# Analog.net
KiCad netlist of a schematic drawn in Altium Designer
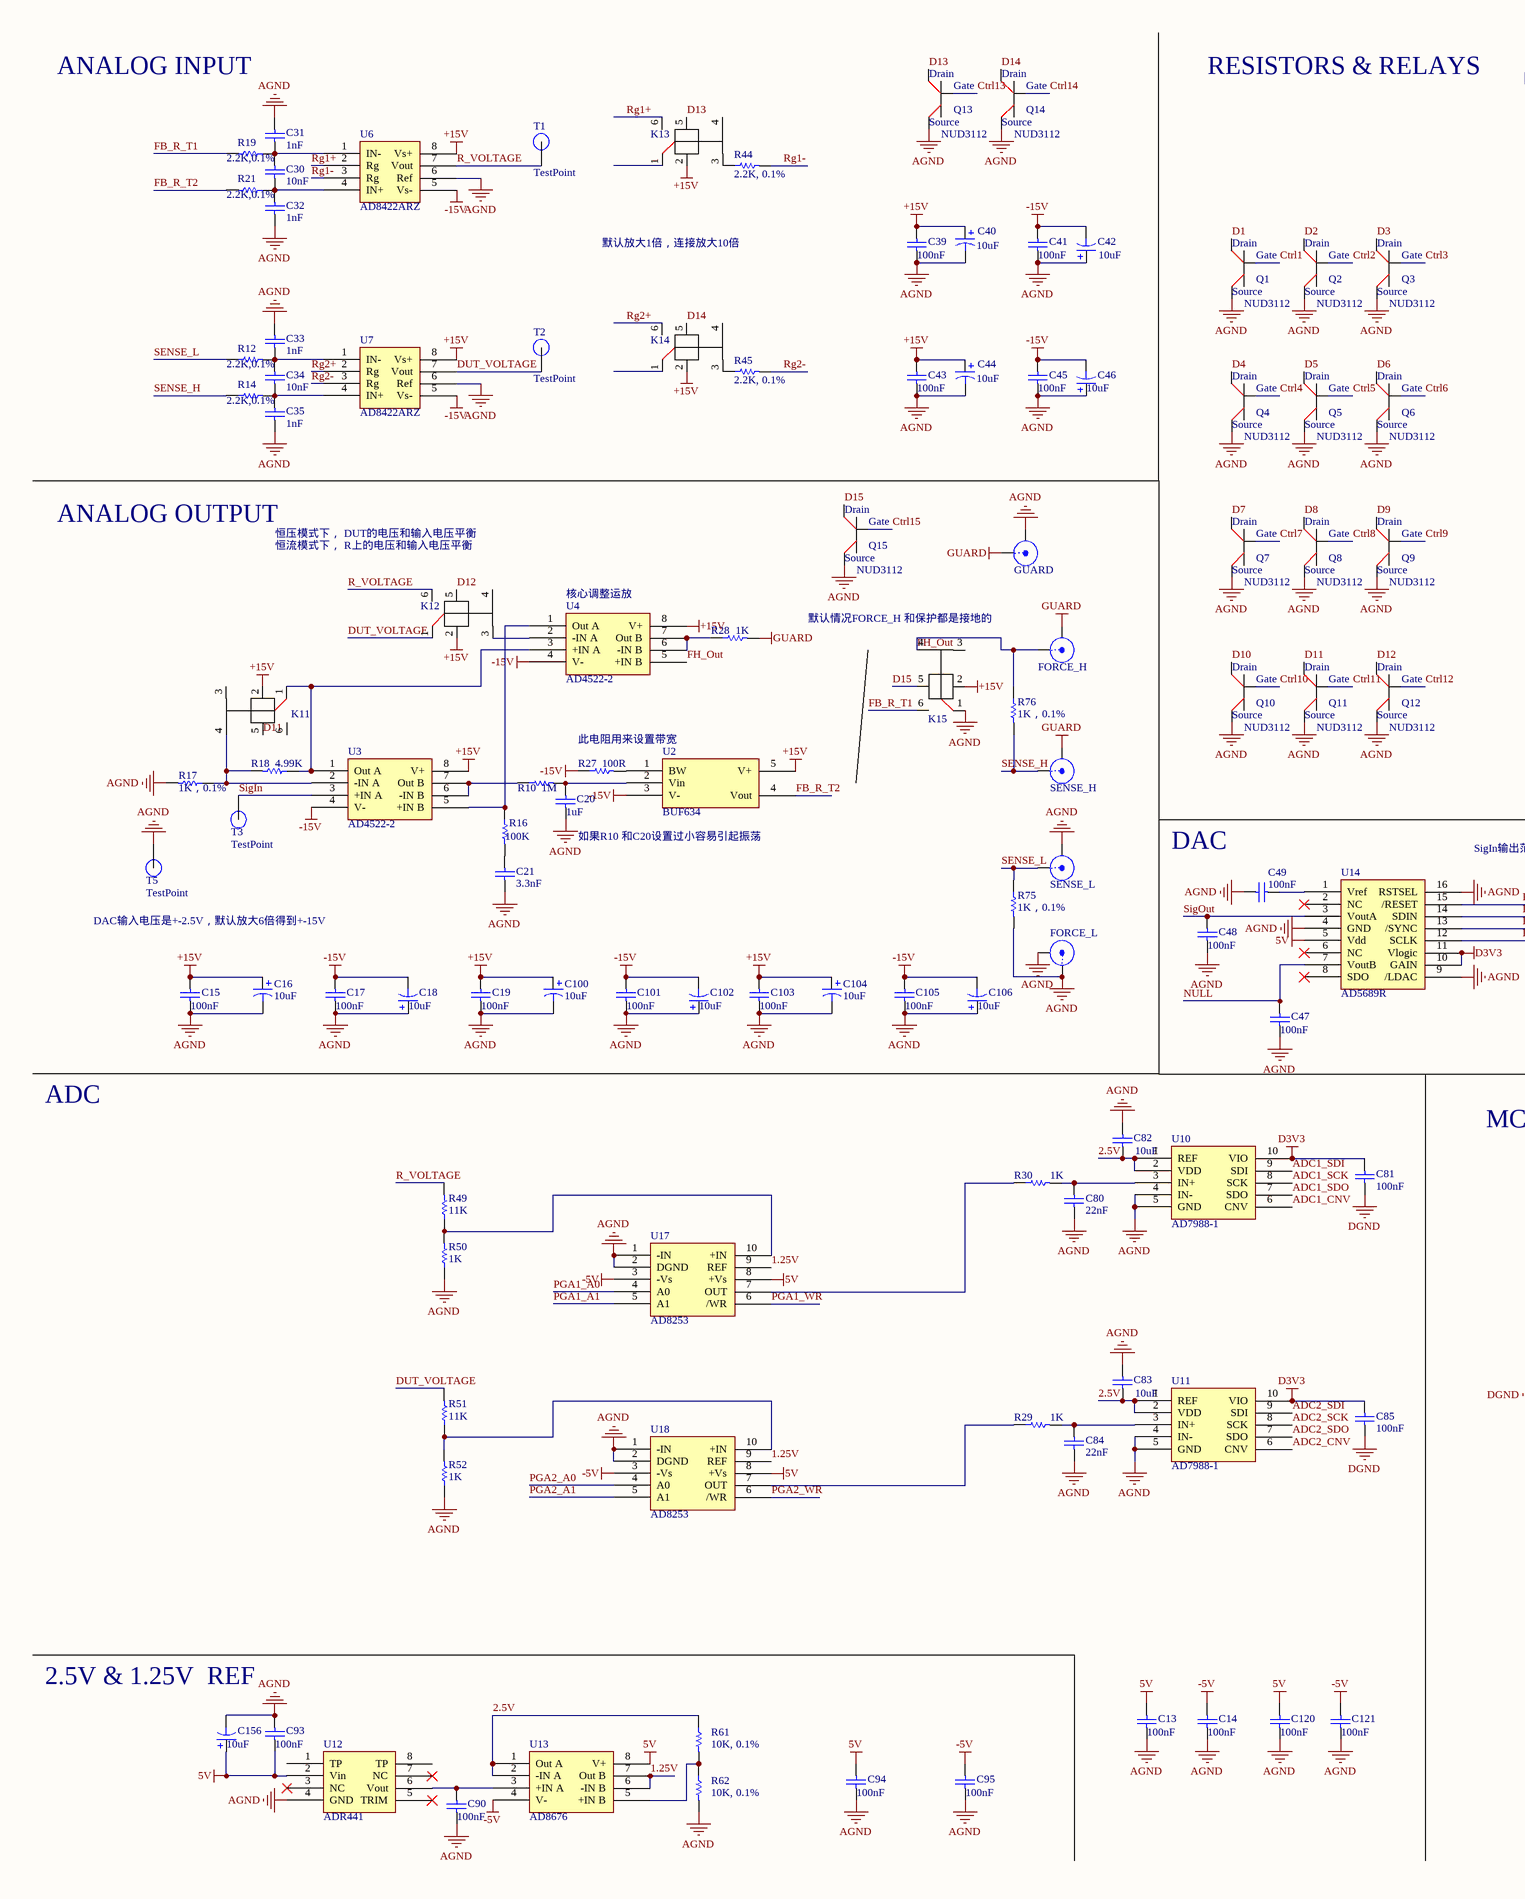
[diagram p0: Analog.SchDoc, left]
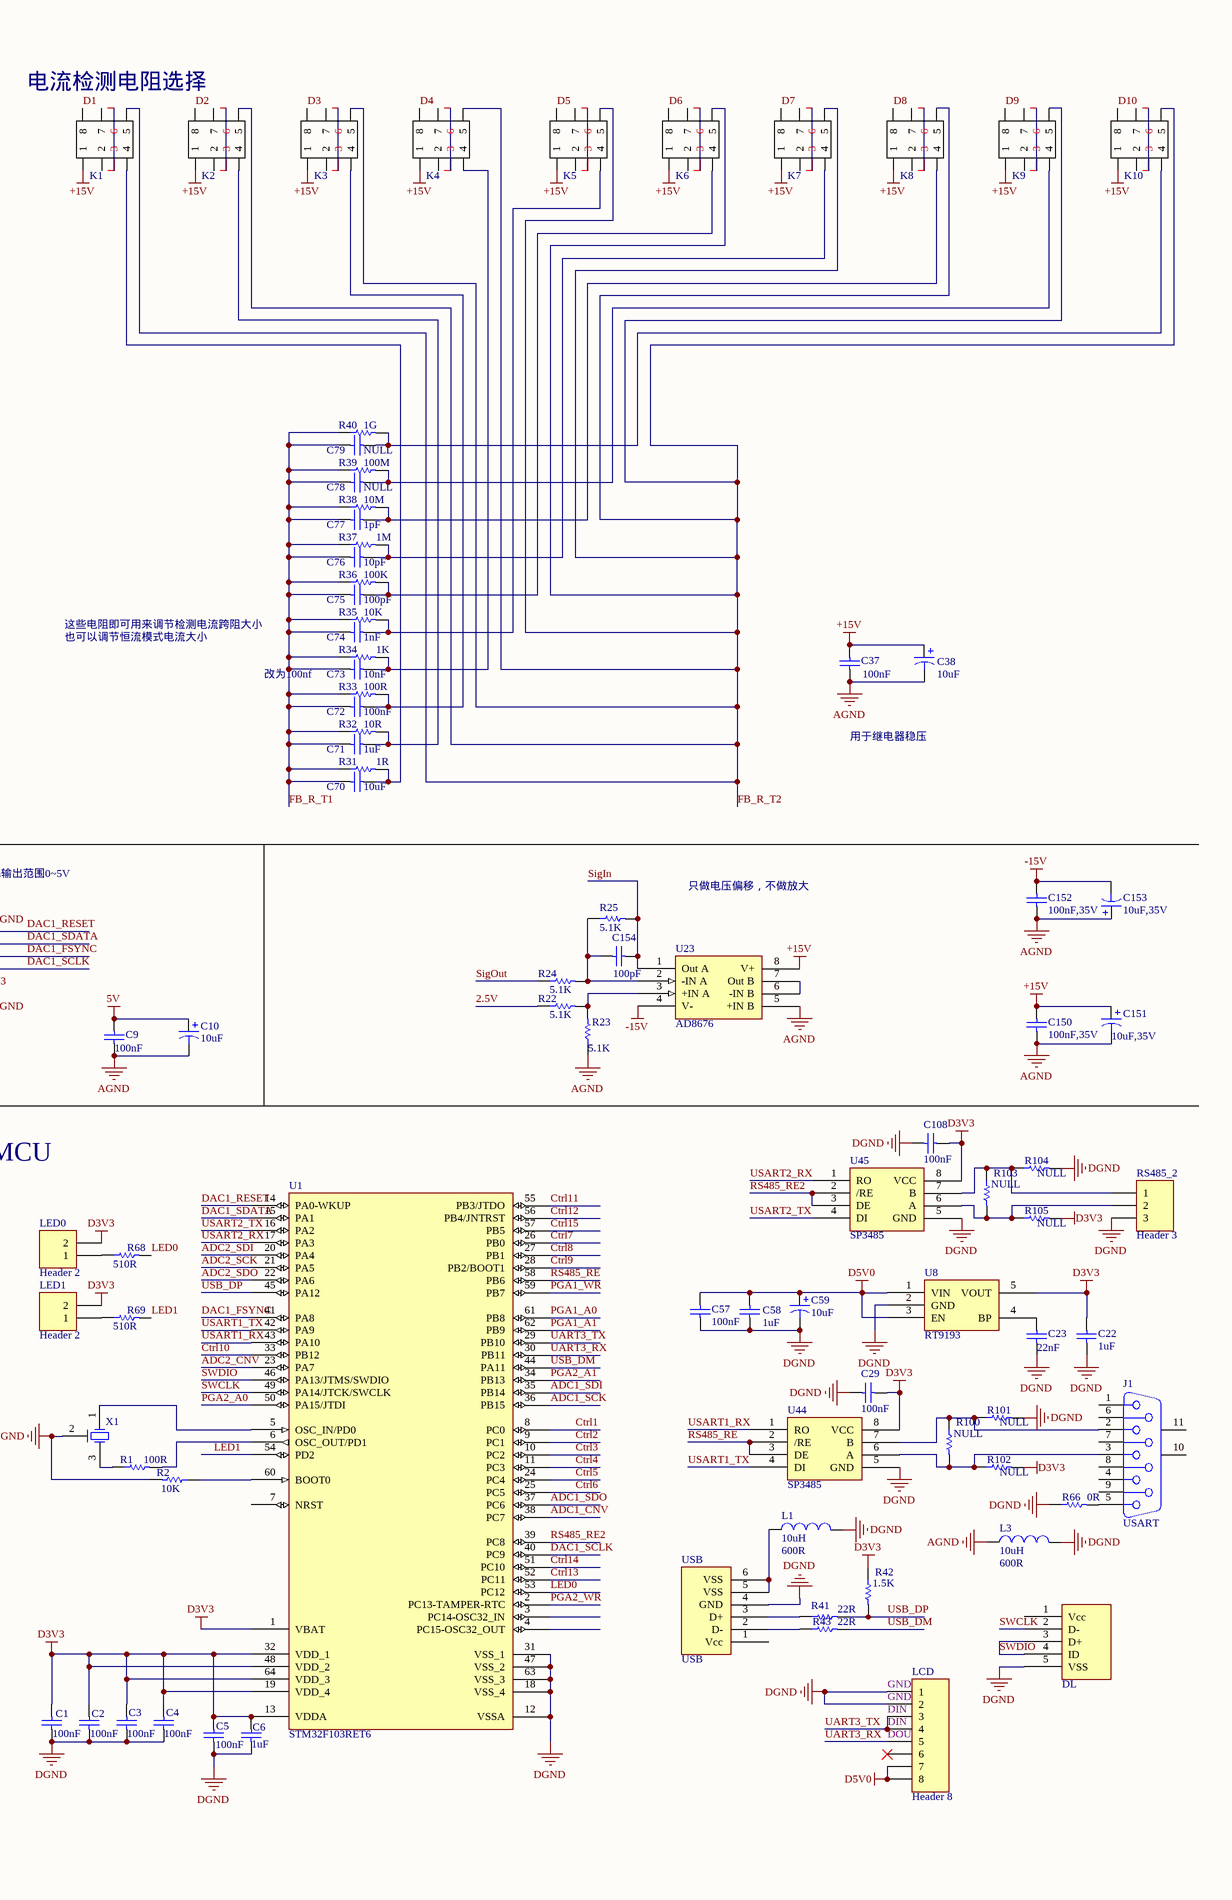
[diagram p1: Analog.SchDoc, right]

(export (version "E")
  (design (tool "Eeschema 10.0.6"))
  (components
    (comp (ref "C1")
      (value "100nF")
      (footprint "BinFeng:0603")
      (description "Capacitor")
      (fields (field (name "PUBLISHER") "Altium Limited"))
      (libsource (lib "Miscellaneous Devices") (part "Cap"))
    )
    (comp (ref "C2")
      (value "100nF")
      (footprint "BinFeng:0603")
      (description "Capacitor")
      (fields (field (name "PUBLISHER") "Altium Limited"))
      (libsource (lib "Miscellaneous Devices") (part "Cap"))
    )
    (comp (ref "C3")
      (value "100nF")
      (footprint "BinFeng:0603")
      (description "Capacitor")
      (fields (field (name "PUBLISHER") "Altium Limited"))
      (libsource (lib "Miscellaneous Devices") (part "Cap"))
    )
    (comp (ref "C4")
      (value "100nF")
      (footprint "BinFeng:0603")
      (description "Capacitor")
      (fields (field (name "PUBLISHER") "Altium Limited"))
      (libsource (lib "Miscellaneous Devices") (part "Cap"))
    )
    (comp (ref "C5")
      (value "100nF")
      (footprint "BinFeng:0603")
      (description "Capacitor")
      (fields (field (name "PUBLISHER") "Altium Limited"))
      (libsource (lib "Miscellaneous Devices") (part "Cap"))
    )
    (comp (ref "C6")
      (value "1uF")
      (footprint "BinFeng:0603")
      (description "Capacitor")
      (fields (field (name "PUBLISHER") "Altium Limited"))
      (libsource (lib "Miscellaneous Devices") (part "Cap"))
    )
    (comp (ref "C9")
      (value "100nF")
      (footprint "0805")
      (description "Capacitor")
      (fields (field (name "PUBLISHER") "Altium Limited"))
      (libsource (lib "Miscellaneous Devices") (part "Cap"))
    )
    (comp (ref "C10")
      (value "10uF")
      (footprint "6032_pol")
      (description "Polarized Capacitor (Radial)")
      (fields (field (name "PUBLISHER") "Altium Limited"))
      (libsource (lib "Miscellaneous Devices") (part "Cap Pol1"))
    )
    (comp (ref "C13")
      (value "100nF")
      (footprint "BinFeng:0603")
      (description "Capacitor")
      (fields (field (name "PUBLISHER") "Altium Limited"))
      (libsource (lib "Miscellaneous Devices") (part "Cap"))
    )
    (comp (ref "C14")
      (value "100nF")
      (footprint "BinFeng:0603")
      (description "Capacitor")
      (fields (field (name "PUBLISHER") "Altium Limited"))
      (libsource (lib "Miscellaneous Devices") (part "Cap"))
    )
    (comp (ref "C15")
      (value "100nF")
      (footprint "0805")
      (description "Capacitor")
      (fields (field (name "PUBLISHER") "Altium Limited"))
      (libsource (lib "Miscellaneous Devices") (part "Cap"))
    )
    (comp (ref "C16")
      (value "10uF")
      (footprint "6032_pol")
      (description "Polarized Capacitor (Radial)")
      (fields (field (name "PUBLISHER") "Altium Limited"))
      (libsource (lib "Miscellaneous Devices") (part "Cap Pol1"))
    )
    (comp (ref "C17")
      (value "100nF")
      (footprint "0805")
      (description "Capacitor")
      (fields (field (name "PUBLISHER") "Altium Limited"))
      (libsource (lib "Miscellaneous Devices") (part "Cap"))
    )
    (comp (ref "C18")
      (value "10uF")
      (footprint "6032_pol")
      (description "Polarized Capacitor (Radial)")
      (fields (field (name "PUBLISHER") "Altium Limited"))
      (libsource (lib "Miscellaneous Devices") (part "Cap Pol1"))
    )
    (comp (ref "C19")
      (value "100nF")
      (footprint "0805")
      (description "Capacitor")
      (fields (field (name "PUBLISHER") "Altium Limited"))
      (libsource (lib "Miscellaneous Devices") (part "Cap"))
    )
    (comp (ref "C20")
      (value "1uF")
      (footprint "BinFeng:0603")
      (description "Capacitor")
      (fields (field (name "PUBLISHER") "Altium Limited"))
      (libsource (lib "Miscellaneous Devices") (part "Cap"))
    )
    (comp (ref "C21")
      (value "3.3nF")
      (footprint "BinFeng:0603")
      (description "Capacitor")
      (fields (field (name "PUBLISHER") "Altium Limited"))
      (libsource (lib "Miscellaneous Devices") (part "Cap"))
    )
    (comp (ref "C22")
      (value "1uF")
      (footprint "BinFeng:0603")
      (description "Capacitor")
      (fields (field (name "PUBLISHER") "Altium Limited"))
      (libsource (lib "Miscellaneous Devices") (part "Cap"))
    )
    (comp (ref "C23")
      (value "22nF")
      (footprint "BinFeng:0603")
      (description "Capacitor")
      (fields (field (name "PUBLISHER") "Altium Limited"))
      (libsource (lib "Miscellaneous Devices") (part "Cap"))
    )
    (comp (ref "C29")
      (value "100nF")
      (footprint "BinFeng:0603")
      (description "Capacitor")
      (fields (field (name "PUBLISHER") "Altium Limited"))
      (libsource (lib "Miscellaneous Devices") (part "Cap"))
    )
    (comp (ref "C30")
      (value "10nF")
      (footprint "BinFeng:0603")
      (description "Capacitor")
      (fields (field (name "PUBLISHER") "Altium Limited"))
      (libsource (lib "Miscellaneous Devices") (part "Cap"))
    )
    (comp (ref "C31")
      (value "1nF")
      (footprint "BinFeng:0603")
      (description "Capacitor")
      (fields (field (name "PUBLISHER") "Altium Limited"))
      (libsource (lib "Miscellaneous Devices") (part "Cap"))
    )
    (comp (ref "C32")
      (value "1nF")
      (footprint "BinFeng:0603")
      (description "Capacitor")
      (fields (field (name "PUBLISHER") "Altium Limited"))
      (libsource (lib "Miscellaneous Devices") (part "Cap"))
    )
    (comp (ref "C33")
      (value "1nF")
      (footprint "BinFeng:0603")
      (description "Capacitor")
      (fields (field (name "PUBLISHER") "Altium Limited"))
      (libsource (lib "Miscellaneous Devices") (part "Cap"))
    )
    (comp (ref "C34")
      (value "10nF")
      (footprint "BinFeng:0603")
      (description "Capacitor")
      (fields (field (name "PUBLISHER") "Altium Limited"))
      (libsource (lib "Miscellaneous Devices") (part "Cap"))
    )
    (comp (ref "C35")
      (value "1nF")
      (footprint "BinFeng:0603")
      (description "Capacitor")
      (fields (field (name "PUBLISHER") "Altium Limited"))
      (libsource (lib "Miscellaneous Devices") (part "Cap"))
    )
    (comp (ref "C37")
      (value "100nF")
      (footprint "0805")
      (description "Capacitor")
      (fields (field (name "PUBLISHER") "Altium Limited"))
      (libsource (lib "Miscellaneous Devices") (part "Cap"))
    )
    (comp (ref "C38")
      (value "10uF")
      (footprint "6032_pol")
      (description "Polarized Capacitor (Radial)")
      (fields (field (name "PUBLISHER") "Altium Limited"))
      (libsource (lib "Miscellaneous Devices") (part "Cap Pol1"))
    )
    (comp (ref "C39")
      (value "100nF")
      (footprint "0805")
      (description "Capacitor")
      (fields (field (name "PUBLISHER") "Altium Limited"))
      (libsource (lib "Miscellaneous Devices") (part "Cap"))
    )
    (comp (ref "C40")
      (value "10uF")
      (footprint "6032_pol")
      (description "Polarized Capacitor (Radial)")
      (fields (field (name "PUBLISHER") "Altium Limited"))
      (libsource (lib "Miscellaneous Devices") (part "Cap Pol1"))
    )
    (comp (ref "C41")
      (value "100nF")
      (footprint "0805")
      (description "Capacitor")
      (fields (field (name "PUBLISHER") "Altium Limited"))
      (libsource (lib "Miscellaneous Devices") (part "Cap"))
    )
    (comp (ref "C42")
      (value "10uF")
      (footprint "6032_pol")
      (description "Polarized Capacitor (Radial)")
      (fields (field (name "PUBLISHER") "Altium Limited"))
      (libsource (lib "Miscellaneous Devices") (part "Cap Pol1"))
    )
    (comp (ref "C43")
      (value "100nF")
      (footprint "0805")
      (description "Capacitor")
      (fields (field (name "PUBLISHER") "Altium Limited"))
      (libsource (lib "Miscellaneous Devices") (part "Cap"))
    )
    (comp (ref "C44")
      (value "10uF")
      (footprint "6032_pol")
      (description "Polarized Capacitor (Radial)")
      (fields (field (name "PUBLISHER") "Altium Limited"))
      (libsource (lib "Miscellaneous Devices") (part "Cap Pol1"))
    )
    (comp (ref "C45")
      (value "100nF")
      (footprint "0805")
      (description "Capacitor")
      (fields (field (name "PUBLISHER") "Altium Limited"))
      (libsource (lib "Miscellaneous Devices") (part "Cap"))
    )
    (comp (ref "C46")
      (value "10uF")
      (footprint "6032_pol")
      (description "Polarized Capacitor (Radial)")
      (fields (field (name "PUBLISHER") "Altium Limited"))
      (libsource (lib "Miscellaneous Devices") (part "Cap Pol1"))
    )
    (comp (ref "C47")
      (value "100nF")
      (footprint "BinFeng:0603")
      (description "Capacitor")
      (fields (field (name "PUBLISHER") "Altium Limited"))
      (libsource (lib "Miscellaneous Devices") (part "Cap"))
    )
    (comp (ref "C48")
      (value "100nF")
      (footprint "BinFeng:0603")
      (description "Capacitor")
      (fields (field (name "PUBLISHER") "Altium Limited"))
      (libsource (lib "Miscellaneous Devices") (part "Cap"))
    )
    (comp (ref "C49")
      (value "100nF")
      (footprint "BinFeng:0603")
      (description "Capacitor")
      (fields (field (name "PUBLISHER") "Altium Limited"))
      (libsource (lib "Miscellaneous Devices") (part "Cap"))
    )
    (comp (ref "C57")
      (value "100nF")
      (footprint "0805")
      (description "Capacitor,100V")
      (fields (field (name "PUBLISHER") "Altium Limited"))
      (libsource (lib "Miscellaneous Devices") (part "Cap"))
    )
    (comp (ref "C58")
      (value "1uF")
      (footprint "0805")
      (description "Capacitor")
      (fields (field (name "PUBLISHER") "Altium Limited"))
      (libsource (lib "Miscellaneous Devices") (part "Cap"))
    )
    (comp (ref "C59")
      (value "10uF")
      (footprint "6032_pol")
      (description "Polarized Capacitor (Radial)")
      (fields (field (name "PUBLISHER") "Altium Limited"))
      (libsource (lib "Miscellaneous Devices") (part "Cap Pol1"))
    )
    (comp (ref "C70")
      (value "10uF")
      (footprint "0805")
      (description "Capacitor")
      (fields (field (name "PUBLISHER") "Altium Limited"))
      (libsource (lib "Miscellaneous Devices") (part "Cap"))
    )
    (comp (ref "C71")
      (value "1uF")
      (footprint "0805")
      (description "Capacitor")
      (fields (field (name "PUBLISHER") "Altium Limited"))
      (libsource (lib "Miscellaneous Devices") (part "Cap"))
    )
    (comp (ref "C72")
      (value "100nF")
      (footprint "0805")
      (description "Capacitor")
      (fields (field (name "PUBLISHER") "Altium Limited"))
      (libsource (lib "Miscellaneous Devices") (part "Cap"))
    )
    (comp (ref "C73")
      (value "10nF")
      (footprint "0805")
      (description "Capacitor")
      (fields (field (name "PUBLISHER") "Altium Limited"))
      (libsource (lib "Miscellaneous Devices") (part "Cap"))
    )
    (comp (ref "C74")
      (value "1nF")
      (footprint "0805")
      (description "Capacitor")
      (fields (field (name "PUBLISHER") "Altium Limited"))
      (libsource (lib "Miscellaneous Devices") (part "Cap"))
    )
    (comp (ref "C75")
      (value "100pF")
      (footprint "0805")
      (description "Capacitor")
      (fields (field (name "PUBLISHER") "Altium Limited"))
      (libsource (lib "Miscellaneous Devices") (part "Cap"))
    )
    (comp (ref "C76")
      (value "10pF")
      (footprint "0805")
      (description "Capacitor")
      (fields (field (name "PUBLISHER") "Altium Limited"))
      (libsource (lib "Miscellaneous Devices") (part "Cap"))
    )
    (comp (ref "C77")
      (value "1pF")
      (footprint "0805")
      (description "Capacitor")
      (fields (field (name "PUBLISHER") "Altium Limited"))
      (libsource (lib "Miscellaneous Devices") (part "Cap"))
    )
    (comp (ref "C78")
      (value "NULL")
      (footprint "0805")
      (description "Capacitor")
      (fields (field (name "PUBLISHER") "Altium Limited"))
      (libsource (lib "Miscellaneous Devices") (part "Cap"))
    )
    (comp (ref "C79")
      (value "NULL")
      (footprint "0805")
      (description "Capacitor")
      (fields (field (name "PUBLISHER") "Altium Limited"))
      (libsource (lib "Miscellaneous Devices") (part "Cap"))
    )
    (comp (ref "C80")
      (value "22nF")
      (footprint "BinFeng:0603")
      (description "Capacitor")
      (fields (field (name "PUBLISHER") "Altium Limited"))
      (libsource (lib "Miscellaneous Devices") (part "Cap"))
    )
    (comp (ref "C81")
      (value "100nF")
      (footprint "BinFeng:0603")
      (description "Capacitor,100V")
      (fields (field (name "PUBLISHER") "Altium Limited"))
      (libsource (lib "Miscellaneous Devices") (part "Cap"))
    )
    (comp (ref "C82")
      (value "10uF")
      (footprint "0805")
      (description "Capacitor")
      (fields (field (name "PUBLISHER") "Altium Limited"))
      (libsource (lib "Miscellaneous Devices") (part "Cap"))
    )
    (comp (ref "C83")
      (value "10uF")
      (footprint "0805")
      (description "Capacitor")
      (fields (field (name "PUBLISHER") "Altium Limited"))
      (libsource (lib "Miscellaneous Devices") (part "Cap"))
    )
    (comp (ref "C84")
      (value "22nF")
      (footprint "BinFeng:0603")
      (description "Capacitor")
      (fields (field (name "PUBLISHER") "Altium Limited"))
      (libsource (lib "Miscellaneous Devices") (part "Cap"))
    )
    (comp (ref "C85")
      (value "100nF")
      (footprint "BinFeng:0603")
      (description "Capacitor,100V")
      (fields (field (name "PUBLISHER") "Altium Limited"))
      (libsource (lib "Miscellaneous Devices") (part "Cap"))
    )
    (comp (ref "C90")
      (value "100nF")
      (footprint "BinFeng:0603")
      (description "Capacitor")
      (fields (field (name "PUBLISHER") "Altium Limited"))
      (libsource (lib "Miscellaneous Devices") (part "Cap"))
    )
    (comp (ref "C93")
      (value "100nF")
      (footprint "BinFeng:0603")
      (description "Capacitor")
      (fields (field (name "PUBLISHER") "Altium Limited"))
      (libsource (lib "Miscellaneous Devices") (part "Cap"))
    )
    (comp (ref "C94")
      (value "100nF")
      (footprint "BinFeng:0603")
      (description "Capacitor")
      (fields (field (name "PUBLISHER") "Altium Limited"))
      (libsource (lib "Miscellaneous Devices") (part "Cap"))
    )
    (comp (ref "C95")
      (value "100nF")
      (footprint "BinFeng:0603")
      (description "Capacitor")
      (fields (field (name "PUBLISHER") "Altium Limited"))
      (libsource (lib "Miscellaneous Devices") (part "Cap"))
    )
    (comp (ref "C100")
      (value "10uF")
      (footprint "6032_pol")
      (description "Polarized Capacitor (Radial)")
      (fields (field (name "PUBLISHER") "Altium Limited"))
      (libsource (lib "Miscellaneous Devices") (part "Cap Pol1"))
    )
    (comp (ref "C101")
      (value "100nF")
      (footprint "0805")
      (description "Capacitor")
      (fields (field (name "PUBLISHER") "Altium Limited"))
      (libsource (lib "Miscellaneous Devices") (part "Cap"))
    )
    (comp (ref "C102")
      (value "10uF")
      (footprint "6032_pol")
      (description "Polarized Capacitor (Radial)")
      (fields (field (name "PUBLISHER") "Altium Limited"))
      (libsource (lib "Miscellaneous Devices") (part "Cap Pol1"))
    )
    (comp (ref "C103")
      (value "100nF")
      (footprint "0805")
      (description "Capacitor")
      (fields (field (name "PUBLISHER") "Altium Limited"))
      (libsource (lib "Miscellaneous Devices") (part "Cap"))
    )
    (comp (ref "C104")
      (value "10uF")
      (footprint "6032_pol")
      (description "Polarized Capacitor (Radial)")
      (fields (field (name "PUBLISHER") "Altium Limited"))
      (libsource (lib "Miscellaneous Devices") (part "Cap Pol1"))
    )
    (comp (ref "C105")
      (value "100nF")
      (footprint "0805")
      (description "Capacitor")
      (fields (field (name "PUBLISHER") "Altium Limited"))
      (libsource (lib "Miscellaneous Devices") (part "Cap"))
    )
    (comp (ref "C106")
      (value "10uF")
      (footprint "6032_pol")
      (description "Polarized Capacitor (Radial)")
      (fields (field (name "PUBLISHER") "Altium Limited"))
      (libsource (lib "Miscellaneous Devices") (part "Cap Pol1"))
    )
    (comp (ref "C108")
      (value "100nF")
      (footprint "BinFeng:0603")
      (description "Capacitor")
      (fields (field (name "PUBLISHER") "Altium Limited"))
      (libsource (lib "Miscellaneous Devices") (part "Cap"))
    )
    (comp (ref "C120")
      (value "100nF")
      (footprint "BinFeng:0603")
      (description "Capacitor")
      (fields (field (name "PUBLISHER") "Altium Limited"))
      (libsource (lib "Miscellaneous Devices") (part "Cap"))
    )
    (comp (ref "C121")
      (value "100nF")
      (footprint "BinFeng:0603")
      (description "Capacitor")
      (fields (field (name "PUBLISHER") "Altium Limited"))
      (libsource (lib "Miscellaneous Devices") (part "Cap"))
    )
    (comp (ref "C150")
      (value "100nF,35V")
      (footprint "BinFeng:0603")
      (description "Capacitor")
      (fields (field (name "Comment") "100nF") (field (name "PUBLISHER") "Altium Limited"))
      (libsource (lib "Miscellaneous Devices") (part "Cap"))
    )
    (comp (ref "C151")
      (value "10uF,35V")
      (footprint "6032_pol")
      (description "Polarized Capacitor (Radial)")
      (fields (field (name "Comment") "10uF") (field (name "PUBLISHER") "Altium Limited"))
      (libsource (lib "Miscellaneous Devices") (part "Cap Pol1"))
    )
    (comp (ref "C152")
      (value "100nF,35V")
      (footprint "BinFeng:0603")
      (description "Capacitor")
      (fields (field (name "Comment") "100nF") (field (name "PUBLISHER") "Altium Limited"))
      (libsource (lib "Miscellaneous Devices") (part "Cap"))
    )
    (comp (ref "C153")
      (value "10uF,35V")
      (footprint "6032_pol")
      (description "Polarized Capacitor (Radial)")
      (fields (field (name "Comment") "10uF") (field (name "PUBLISHER") "Altium Limited"))
      (libsource (lib "Miscellaneous Devices") (part "Cap Pol1"))
    )
    (comp (ref "C154")
      (value "100pF")
      (footprint "0805")
      (description "Capacitor")
      (fields (field (name "PUBLISHER") "Altium Limited"))
      (libsource (lib "Miscellaneous Devices") (part "Cap"))
    )
    (comp (ref "C156")
      (value "10uF")
      (footprint "6032_pol")
      (description "Polarized Capacitor (Radial)")
      (fields (field (name "PUBLISHER") "Altium Limited"))
      (libsource (lib "Miscellaneous Devices") (part "Cap Pol1"))
    )
    (comp (ref "DL")
      (value "USB_5pin")
      (footprint "USBmicro_B")
      (libsource (lib "BinFeng_Connectors") (part "USB_5pin"))
    )
    (comp (ref "FORCE_H")
      (value "SMB")
      (footprint "SMA")
      (description "SMB Straight Connector")
      (fields (field (name "PUBLISHER") "Altium Limited"))
      (libsource (lib "Miscellaneous Connectors") (part "SMB"))
    )
    (comp (ref "FORCE_L")
      (value "SMB")
      (footprint "SMA")
      (description "SMB Straight Connector")
      (fields (field (name "PUBLISHER") "Altium Limited"))
      (libsource (lib "Miscellaneous Connectors") (part "SMB"))
    )
    (comp (ref "GUARD")
      (value "SMB")
      (footprint "SMA")
      (description "SMB Straight Connector")
      (fields (field (name "PUBLISHER") "Altium Limited"))
      (libsource (lib "Miscellaneous Connectors") (part "SMB"))
    )
    (comp (ref "J1")
      (value "USART")
      (footprint "DSUB1.385-2H9")
      (description "Receptacle Assembly, 9 Position, Right Angle")
      (fields (field (name "PUBLISHER") "Altium Limited"))
      (libsource (lib "Miscellaneous Connectors") (part "D Connector 9"))
    )
    (comp (ref "K1")
      (value "AXICOM IM")
      (footprint "AXICOM_IM06")
      (libsource (lib "BinFeng_IC") (part "AXiCOM IM05"))
    )
    (comp (ref "K2")
      (value "AXICOM IM")
      (footprint "AXICOM_IM06")
      (libsource (lib "BinFeng_IC") (part "AXiCOM IM05"))
    )
    (comp (ref "K3")
      (value "AXICOM IM")
      (footprint "AXICOM_IM06")
      (libsource (lib "BinFeng_IC") (part "AXiCOM IM05"))
    )
    (comp (ref "K4")
      (value "AXICOM IM")
      (footprint "AXICOM_IM06")
      (libsource (lib "BinFeng_IC") (part "AXiCOM IM05"))
    )
    (comp (ref "K5")
      (value "AXICOM IM")
      (footprint "AXICOM_IM06")
      (libsource (lib "BinFeng_IC") (part "AXiCOM IM05"))
    )
    (comp (ref "K6")
      (value "AXICOM IM")
      (footprint "AXICOM_IM06")
      (libsource (lib "BinFeng_IC") (part "AXiCOM IM05"))
    )
    (comp (ref "K7")
      (value "AXICOM IM")
      (footprint "AXICOM_IM06")
      (libsource (lib "BinFeng_IC") (part "AXiCOM IM05"))
    )
    (comp (ref "K8")
      (value "AXICOM IM")
      (footprint "AXICOM_IM06")
      (libsource (lib "BinFeng_IC") (part "AXiCOM IM05"))
    )
    (comp (ref "K9")
      (value "AXICOM IM")
      (footprint "AXICOM_IM06")
      (libsource (lib "BinFeng_IC") (part "AXiCOM IM05"))
    )
    (comp (ref "K10")
      (value "AXICOM IM")
      (footprint "AXICOM_IM06")
      (libsource (lib "BinFeng_IC") (part "AXiCOM IM05"))
    )
    (comp (ref "K11")
      (value "Relay")
      (footprint "Relay_OMRON5V")
      (description "Relay OMRON")
      (libsource (lib "BinFeng_IC") (part "Relay_OMRON5V"))
    )
    (comp (ref "K12")
      (value "Relay")
      (footprint "Relay_OMRON5V")
      (description "Relay OMRON")
      (libsource (lib "BinFeng_IC") (part "Relay_OMRON5V"))
    )
    (comp (ref "K13")
      (value "Relay")
      (footprint "Relay_OMRON5V")
      (description "Relay OMRON")
      (libsource (lib "BinFeng_IC") (part "Relay_OMRON5V"))
    )
    (comp (ref "K14")
      (value "Relay")
      (footprint "Relay_OMRON5V")
      (description "Relay OMRON")
      (libsource (lib "BinFeng_IC") (part "Relay_OMRON5V"))
    )
    (comp (ref "K15")
      (value "Relay")
      (footprint "Relay_OMRON5V")
      (description "Relay OMRON")
      (libsource (lib "BinFeng_IC") (part "Relay_OMRON5V"))
    )
    (comp (ref "L1")
      (value "10uH")
      (footprint "0805")
      (description "Inductor")
      (fields (field (name "ALTIUM_VALUE") "600R") (field (name "PUBLISHER") "Altium Limited"))
      (libsource (lib "Miscellaneous Devices") (part "Inductor"))
    )
    (comp (ref "L3")
      (value "10uH")
      (footprint "1206")
      (description "Inductor")
      (fields (field (name "ALTIUM_VALUE") "600R") (field (name "PUBLISHER") "Altium Limited"))
      (libsource (lib "Miscellaneous Devices") (part "Inductor"))
    )
    (comp (ref "LCD")
      (value "Header 8")
      (footprint "HDR1X8")
      (description "Header, 8-Pin")
      (fields (field (name "PUBLISHER") "Altium Limited"))
      (libsource (lib "Miscellaneous Connectors") (part "Header 8"))
    )
    (comp (ref "LED0")
      (value "Header 2")
      (footprint "HDR1X2")
      (description "Header, 2-Pin")
      (fields (field (name "PUBLISHER") "Altium Limited"))
      (libsource (lib "Miscellaneous Connectors") (part "Header 2"))
    )
    (comp (ref "LED1")
      (value "Header 2")
      (footprint "HDR1X2")
      (description "Header, 2-Pin")
      (fields (field (name "PUBLISHER") "Altium Limited"))
      (libsource (lib "Miscellaneous Connectors") (part "Header 2"))
    )
    (comp (ref "Q1")
      (value "NUD3112")
      (footprint "SOT_23")
      (description "Relay Driver 5V Supply")
      (libsource (lib "BinFeng_IC") (part "NUD3105"))
    )
    (comp (ref "Q2")
      (value "NUD3112")
      (footprint "SOT_23")
      (description "Relay Driver 5V Supply")
      (libsource (lib "BinFeng_IC") (part "NUD3105"))
    )
    (comp (ref "Q3")
      (value "NUD3112")
      (footprint "SOT_23")
      (description "Relay Driver 5V Supply")
      (libsource (lib "BinFeng_IC") (part "NUD3105"))
    )
    (comp (ref "Q4")
      (value "NUD3112")
      (footprint "SOT_23")
      (description "Relay Driver 5V Supply")
      (libsource (lib "BinFeng_IC") (part "NUD3105"))
    )
    (comp (ref "Q5")
      (value "NUD3112")
      (footprint "SOT_23")
      (description "Relay Driver 5V Supply")
      (libsource (lib "BinFeng_IC") (part "NUD3105"))
    )
    (comp (ref "Q6")
      (value "NUD3112")
      (footprint "SOT_23")
      (description "Relay Driver 5V Supply")
      (libsource (lib "BinFeng_IC") (part "NUD3105"))
    )
    (comp (ref "Q7")
      (value "NUD3112")
      (footprint "SOT_23")
      (description "Relay Driver 5V Supply")
      (libsource (lib "BinFeng_IC") (part "NUD3105"))
    )
    (comp (ref "Q8")
      (value "NUD3112")
      (footprint "SOT_23")
      (description "Relay Driver 5V Supply")
      (libsource (lib "BinFeng_IC") (part "NUD3105"))
    )
    (comp (ref "Q9")
      (value "NUD3112")
      (footprint "SOT_23")
      (description "Relay Driver 5V Supply")
      (libsource (lib "BinFeng_IC") (part "NUD3105"))
    )
    (comp (ref "Q10")
      (value "NUD3112")
      (footprint "SOT_23")
      (description "Relay Driver 5V Supply")
      (libsource (lib "BinFeng_IC") (part "NUD3105"))
    )
    (comp (ref "Q11")
      (value "NUD3112")
      (footprint "SOT_23")
      (description "Relay Driver 5V Supply")
      (libsource (lib "BinFeng_IC") (part "NUD3105"))
    )
    (comp (ref "Q12")
      (value "NUD3112")
      (footprint "SOT_23")
      (description "Relay Driver 5V Supply")
      (libsource (lib "BinFeng_IC") (part "NUD3105"))
    )
    (comp (ref "Q13")
      (value "NUD3112")
      (footprint "SOT_23")
      (description "Relay Driver 5V Supply")
      (libsource (lib "BinFeng_IC") (part "NUD3105"))
    )
    (comp (ref "Q14")
      (value "NUD3112")
      (footprint "SOT_23")
      (description "Relay Driver 5V Supply")
      (libsource (lib "BinFeng_IC") (part "NUD3105"))
    )
    (comp (ref "Q15")
      (value "NUD3112")
      (footprint "SOT23")
      (description "Relay Driver 5V Supply")
      (libsource (lib "BinFeng_IC") (part "NUD3105"))
    )
    (comp (ref "R1")
      (value "100R")
      (footprint "BinFeng:0603")
      (description "Resistor")
      (fields (field (name "PUBLISHER") "Altium Limited"))
      (libsource (lib "Miscellaneous Devices") (part "Res1"))
    )
    (comp (ref "R2")
      (value "10K")
      (footprint "BinFeng:0603")
      (description "Resistor")
      (fields (field (name "PUBLISHER") "Altium Limited"))
      (libsource (lib "Miscellaneous Devices") (part "Res1"))
    )
    (comp (ref "R10")
      (value "1M")
      (footprint "BinFeng:0603")
      (description "Resistor")
      (fields (field (name "PUBLISHER") "Altium Limited"))
      (libsource (lib "Miscellaneous Devices") (part "Res1"))
    )
    (comp (ref "R12")
      (value "2.2K,0.1%")
      (footprint "BinFeng:0603")
      (description "Resistor")
      (fields (field (name "PUBLISHER") "Altium Limited"))
      (libsource (lib "Miscellaneous Devices") (part "Res1"))
    )
    (comp (ref "R14")
      (value "2.2K,0.1%")
      (footprint "BinFeng:0603")
      (description "Resistor")
      (fields (field (name "PUBLISHER") "Altium Limited"))
      (libsource (lib "Miscellaneous Devices") (part "Res1"))
    )
    (comp (ref "R16")
      (value "100K")
      (footprint "BinFeng:0603")
      (description "Resistor")
      (fields (field (name "PUBLISHER") "Altium Limited"))
      (libsource (lib "Miscellaneous Devices") (part "Res1"))
    )
    (comp (ref "R17")
      (value "1K，0.1%")
      (footprint "BinFeng:0603")
      (description "Resistor")
      (fields (field (name "PUBLISHER") "Altium Limited"))
      (libsource (lib "Miscellaneous Devices") (part "Res1"))
    )
    (comp (ref "R18")
      (value "4.99K")
      (footprint "BinFeng:0603")
      (description "Resistor")
      (fields (field (name "PUBLISHER") "Altium Limited"))
      (libsource (lib "Miscellaneous Devices") (part "Res1"))
    )
    (comp (ref "R19")
      (value "2.2K,0.1%")
      (footprint "BinFeng:0603")
      (description "Resistor")
      (fields (field (name "PUBLISHER") "Altium Limited"))
      (libsource (lib "Miscellaneous Devices") (part "Res1"))
    )
    (comp (ref "R21")
      (value "2.2K,0.1%")
      (footprint "BinFeng:0603")
      (description "Resistor")
      (fields (field (name "PUBLISHER") "Altium Limited"))
      (libsource (lib "Miscellaneous Devices") (part "Res1"))
    )
    (comp (ref "R22")
      (value "5.1K")
      (footprint "0805")
      (description "Resistor")
      (fields (field (name "PUBLISHER") "Altium Limited"))
      (libsource (lib "Miscellaneous Devices") (part "Res1"))
    )
    (comp (ref "R23")
      (value "5.1K")
      (footprint "0805")
      (description "Resistor")
      (fields (field (name "PUBLISHER") "Altium Limited"))
      (libsource (lib "Miscellaneous Devices") (part "Res1"))
    )
    (comp (ref "R24")
      (value "5.1K")
      (footprint "0805")
      (description "Resistor")
      (fields (field (name "PUBLISHER") "Altium Limited"))
      (libsource (lib "Miscellaneous Devices") (part "Res1"))
    )
    (comp (ref "R25")
      (value "5.1K")
      (footprint "0805")
      (description "Resistor")
      (fields (field (name "PUBLISHER") "Altium Limited"))
      (libsource (lib "Miscellaneous Devices") (part "Res1"))
    )
    (comp (ref "R27")
      (value "100R")
      (footprint "BinFeng:0603")
      (description "Resistor")
      (fields (field (name "PUBLISHER") "Altium Limited"))
      (libsource (lib "Miscellaneous Devices") (part "Res1"))
    )
    (comp (ref "R28")
      (value "1K")
      (footprint "BinFeng:0603")
      (description "Resistor")
      (fields (field (name "PUBLISHER") "Altium Limited"))
      (libsource (lib "Miscellaneous Devices") (part "Res1"))
    )
    (comp (ref "R29")
      (value "1K")
      (footprint "BinFeng:0603")
      (description "Resistor")
      (fields (field (name "PUBLISHER") "Altium Limited"))
      (libsource (lib "Miscellaneous Devices") (part "Res1"))
    )
    (comp (ref "R30")
      (value "1K")
      (footprint "BinFeng:0603")
      (description "Resistor")
      (fields (field (name "PUBLISHER") "Altium Limited"))
      (libsource (lib "Miscellaneous Devices") (part "Res1"))
    )
    (comp (ref "R31")
      (value "1R")
      (footprint "0805")
      (description "Resistor")
      (fields (field (name "PUBLISHER") "Altium Limited"))
      (libsource (lib "Miscellaneous Devices") (part "Res1"))
    )
    (comp (ref "R32")
      (value "10R")
      (footprint "0805")
      (description "Resistor")
      (fields (field (name "PUBLISHER") "Altium Limited"))
      (libsource (lib "Miscellaneous Devices") (part "Res1"))
    )
    (comp (ref "R33")
      (value "100R")
      (footprint "0805")
      (description "Resistor")
      (fields (field (name "PUBLISHER") "Altium Limited"))
      (libsource (lib "Miscellaneous Devices") (part "Res1"))
    )
    (comp (ref "R34")
      (value "1K")
      (footprint "0805")
      (description "Resistor")
      (fields (field (name "PUBLISHER") "Altium Limited"))
      (libsource (lib "Miscellaneous Devices") (part "Res1"))
    )
    (comp (ref "R35")
      (value "10K")
      (footprint "0805")
      (description "Resistor")
      (fields (field (name "PUBLISHER") "Altium Limited"))
      (libsource (lib "Miscellaneous Devices") (part "Res1"))
    )
    (comp (ref "R36")
      (value "100K")
      (footprint "0805")
      (description "Resistor")
      (fields (field (name "PUBLISHER") "Altium Limited"))
      (libsource (lib "Miscellaneous Devices") (part "Res1"))
    )
    (comp (ref "R37")
      (value "1M")
      (footprint "0805")
      (description "Resistor")
      (fields (field (name "PUBLISHER") "Altium Limited"))
      (libsource (lib "Miscellaneous Devices") (part "Res1"))
    )
    (comp (ref "R38")
      (value "10M")
      (footprint "0805")
      (description "Resistor")
      (fields (field (name "PUBLISHER") "Altium Limited"))
      (libsource (lib "Miscellaneous Devices") (part "Res1"))
    )
    (comp (ref "R39")
      (value "100M")
      (footprint "0805")
      (description "Resistor")
      (fields (field (name "PUBLISHER") "Altium Limited"))
      (libsource (lib "Miscellaneous Devices") (part "Res1"))
    )
    (comp (ref "R40")
      (value "1G")
      (footprint "0805")
      (description "Resistor")
      (fields (field (name "PUBLISHER") "Altium Limited"))
      (libsource (lib "Miscellaneous Devices") (part "Res1"))
    )
    (comp (ref "R41")
      (value "22R")
      (footprint "BinFeng:0402")
      (description "Resistor")
      (fields (field (name "PUBLISHER") "Altium Limited"))
      (libsource (lib "Miscellaneous Devices") (part "Res1"))
    )
    (comp (ref "R42")
      (value "1.5K")
      (footprint "BinFeng:0402")
      (description "Resistor")
      (fields (field (name "PUBLISHER") "Altium Limited"))
      (libsource (lib "Miscellaneous Devices") (part "Res1"))
    )
    (comp (ref "R43")
      (value "22R")
      (footprint "BinFeng:0402")
      (description "Resistor")
      (fields (field (name "PUBLISHER") "Altium Limited"))
      (libsource (lib "Miscellaneous Devices") (part "Res1"))
    )
    (comp (ref "R44")
      (value "2.2K, 0.1%")
      (footprint "0603")
      (description "Resistor")
      (fields (field (name "PUBLISHER") "Altium Limited"))
      (libsource (lib "Miscellaneous Devices") (part "Res1"))
    )
    (comp (ref "R45")
      (value "2.2K, 0.1%")
      (footprint "0603")
      (description "Resistor")
      (fields (field (name "PUBLISHER") "Altium Limited"))
      (libsource (lib "Miscellaneous Devices") (part "Res1"))
    )
    (comp (ref "R49")
      (value "11K")
      (footprint "BinFeng:0603")
      (description "Resistor")
      (fields (field (name "PUBLISHER") "Altium Limited"))
      (libsource (lib "Miscellaneous Devices") (part "Res1"))
    )
    (comp (ref "R50")
      (value "1K")
      (footprint "BinFeng:0603")
      (description "Resistor")
      (fields (field (name "PUBLISHER") "Altium Limited"))
      (libsource (lib "Miscellaneous Devices") (part "Res1"))
    )
    (comp (ref "R51")
      (value "11K")
      (footprint "BinFeng:0603")
      (description "Resistor")
      (fields (field (name "PUBLISHER") "Altium Limited"))
      (libsource (lib "Miscellaneous Devices") (part "Res1"))
    )
    (comp (ref "R52")
      (value "1K")
      (footprint "BinFeng:0603")
      (description "Resistor")
      (fields (field (name "PUBLISHER") "Altium Limited"))
      (libsource (lib "Miscellaneous Devices") (part "Res1"))
    )
    (comp (ref "R61")
      (value "10K, 0.1%")
      (footprint "BinFeng:0603")
      (description "Resistor")
      (fields (field (name "PUBLISHER") "Altium Limited"))
      (libsource (lib "Miscellaneous Devices") (part "Res1"))
    )
    (comp (ref "R62")
      (value "10K, 0.1%")
      (footprint "BinFeng:0603")
      (description "Resistor")
      (fields (field (name "PUBLISHER") "Altium Limited"))
      (libsource (lib "Miscellaneous Devices") (part "Res1"))
    )
    (comp (ref "R66")
      (value "0R")
      (footprint "BinFeng:0402")
      (description "Resistor")
      (fields (field (name "PUBLISHER") "Altium Limited"))
      (libsource (lib "Miscellaneous Devices") (part "Res1"))
    )
    (comp (ref "R68")
      (value "510R")
      (footprint "BinFeng:0603")
      (description "Resistor")
      (fields (field (name "PUBLISHER") "Altium Limited"))
      (libsource (lib "Miscellaneous Devices") (part "Res1"))
    )
    (comp (ref "R69")
      (value "510R")
      (footprint "BinFeng:0603")
      (description "Resistor")
      (fields (field (name "PUBLISHER") "Altium Limited"))
      (libsource (lib "Miscellaneous Devices") (part "Res1"))
    )
    (comp (ref "R75")
      (value "1K，0.1%")
      (footprint "BinFeng:0603")
      (description "Resistor")
      (fields (field (name "PUBLISHER") "Altium Limited"))
      (libsource (lib "Miscellaneous Devices") (part "Res1"))
    )
    (comp (ref "R76")
      (value "1K，0.1%")
      (footprint "BinFeng:0603")
      (description "Resistor")
      (fields (field (name "PUBLISHER") "Altium Limited"))
      (libsource (lib "Miscellaneous Devices") (part "Res1"))
    )
    (comp (ref "R100")
      (value "NULL")
      (footprint "BinFeng:0603")
      (description "Resistor")
      (fields (field (name "PUBLISHER") "Altium Limited"))
      (libsource (lib "Miscellaneous Devices") (part "Res1"))
    )
    (comp (ref "R101")
      (value "NULL")
      (footprint "BinFeng:0603")
      (description "Resistor")
      (fields (field (name "PUBLISHER") "Altium Limited"))
      (libsource (lib "Miscellaneous Devices") (part "Res1"))
    )
    (comp (ref "R102")
      (value "NULL")
      (footprint "BinFeng:0603")
      (description "Resistor")
      (fields (field (name "PUBLISHER") "Altium Limited"))
      (libsource (lib "Miscellaneous Devices") (part "Res1"))
    )
    (comp (ref "R103")
      (value "NULL")
      (footprint "BinFeng:0603")
      (description "Resistor")
      (fields (field (name "PUBLISHER") "Altium Limited"))
      (libsource (lib "Miscellaneous Devices") (part "Res1"))
    )
    (comp (ref "R104")
      (value "NULL")
      (footprint "BinFeng:0603")
      (description "Resistor")
      (fields (field (name "PUBLISHER") "Altium Limited"))
      (libsource (lib "Miscellaneous Devices") (part "Res1"))
    )
    (comp (ref "R105")
      (value "NULL")
      (footprint "BinFeng:0603")
      (description "Resistor")
      (fields (field (name "PUBLISHER") "Altium Limited"))
      (libsource (lib "Miscellaneous Devices") (part "Res1"))
    )
    (comp (ref "RS485_2")
      (value "Header 3")
      (footprint "HDR1X3")
      (description "Header, 3-Pin")
      (fields (field (name "PUBLISHER") "Altium Limited"))
      (libsource (lib "Miscellaneous Connectors") (part "Header 3"))
    )
    (comp (ref "SENSE_H")
      (value "SMB")
      (footprint "SMA")
      (description "SMB Straight Connector")
      (fields (field (name "PUBLISHER") "Altium Limited"))
      (libsource (lib "Miscellaneous Connectors") (part "SMB"))
    )
    (comp (ref "SENSE_L")
      (value "SMB")
      (footprint "SMA")
      (description "SMB Straight Connector")
      (fields (field (name "PUBLISHER") "Altium Limited"))
      (libsource (lib "Miscellaneous Connectors") (part "SMB"))
    )
    (comp (ref "T1")
      (value "TestPoint")
      (footprint "TestPoint")
      (libsource (lib "BinFeng_IC") (part "TestPoint"))
    )
    (comp (ref "T2")
      (value "TestPoint")
      (footprint "TestPoint")
      (libsource (lib "BinFeng_IC") (part "TestPoint"))
    )
    (comp (ref "T3")
      (value "TestPoint")
      (footprint "TestPoint")
      (libsource (lib "BinFeng_IC") (part "TestPoint"))
    )
    (comp (ref "T5")
      (value "TestPoint")
      (footprint "TestPoint")
      (libsource (lib "BinFeng_IC") (part "TestPoint"))
    )
    (comp (ref "U1")
      (value "STM32F103RET6")
      (footprint "LQFP64_N")
      (description "STM32 ARM-based 32-bit MCU with 128 Kbytes Flash, 64-pin LQFP, Industrial Temperature")
      (fields (field (name "PUBLISHER") "Altium Limited"))
      (libsource (lib "ST Microcontroller 32-Bit STM32") (part "STM32F103RBT6"))
    )
    (comp (ref "U2") (value "BUF634") (footprint "PSFM-T5") (libsource (lib "BinFeng_IC") (part "BUF634")))
    (comp (ref "U3") (value "AD4522-2") (footprint "SO-8N") (libsource (lib "BinFeng_IC") (part "AD8676")))
    (comp (ref "U4") (value "AD4522-2") (footprint "SO-8N") (libsource (lib "BinFeng_IC") (part "AD8676")))
    (comp (ref "U6") (value "AD8422ARZ") (footprint "SO-8N") (libsource (lib "BinFeng_IC") (part "AD8422")))
    (comp (ref "U7") (value "AD8422ARZ") (footprint "SO-8N") (libsource (lib "BinFeng_IC") (part "AD8422")))
    (comp (ref "U8") (value "RT9193") (footprint "SOT-23-5") (libsource (lib "BinFeng_IC") (part "RT9193")))
    (comp (ref "U10")
      (value "AD7988-1")
      (footprint "MSOP10")
      (libsource (lib "BinFeng_IC") (part "AD7988-1"))
    )
    (comp (ref "U11")
      (value "AD7988-1")
      (footprint "MSOP10")
      (libsource (lib "BinFeng_IC") (part "AD7988-1"))
    )
    (comp (ref "U12")
      (value "ADR441")
      (footprint "SO-8N")
      (description "Ultralow Noise, XFET Voltage References")
      (libsource (lib "BinFeng_IC") (part "ADR441"))
    )
    (comp (ref "U13") (value "AD8676") (footprint "SO-8N") (libsource (lib "BinFeng_IC") (part "AD8676")))
    (comp (ref "U14") (value "AD5689R") (footprint "TSSOP16") (libsource (lib "BinFeng_IC") (part "AD5687R")))
    (comp (ref "U17") (value "AD8253") (footprint "RM-10") (libsource (lib "BinFeng_IC") (part "AD8253")))
    (comp (ref "U18") (value "AD8253") (footprint "RM-10") (libsource (lib "BinFeng_IC") (part "AD8253")))
    (comp (ref "U23") (value "AD8676") (footprint "SO-8N") (libsource (lib "BinFeng_IC") (part "AD8676")))
    (comp (ref "U44") (value "SP3485") (footprint "SO-8N") (libsource (lib "BinFeng_IC") (part "SP3485")))
    (comp (ref "U45") (value "SP3485") (footprint "SO-8N") (libsource (lib "BinFeng_IC") (part "SP3485")))
    (comp (ref "USB")
      (value "USB")
      (footprint "USB_A")
      (description "USB interface")
      (libsource (lib "BinFeng_Connectors") (part "USB_Normal"))
    )
    (comp (ref "X1") (value "8M smd") (footprint "8Mhz_XTAL") (libsource (lib "Schlib1") (part "8M smd")))
  )
  (nets
    (net (code "1") (name "+15V") (class "Default")
      (node (ref "C100") (pin "1") (pinfunction "1_1") (pintype "passive"))
      (node (ref "C103") (pin "2") (pinfunction "2_2") (pintype "passive"))
      (node (ref "C104") (pin "1") (pinfunction "1_1") (pintype "passive"))
      (node (ref "C15") (pin "2") (pinfunction "2_2") (pintype "passive"))
      (node (ref "C150") (pin "2") (pinfunction "2_2") (pintype "passive"))
      (node (ref "C151") (pin "1") (pinfunction "1_1") (pintype "passive"))
      (node (ref "C16") (pin "1") (pinfunction "1_1") (pintype "passive"))
      (node (ref "C19") (pin "2") (pinfunction "2_2") (pintype "passive"))
      (node (ref "C37") (pin "2") (pinfunction "2_2") (pintype "passive"))
      (node (ref "C38") (pin "1") (pinfunction "1_1") (pintype "passive"))
      (node (ref "C39") (pin "2") (pinfunction "2_2") (pintype "passive"))
      (node (ref "C40") (pin "1") (pinfunction "1_1") (pintype "passive"))
      (node (ref "C43") (pin "2") (pinfunction "2_2") (pintype "passive"))
      (node (ref "C44") (pin "1") (pinfunction "1_1") (pintype "passive"))
      (node (ref "K1") (pin "1") (pinfunction "1_1") (pintype "passive"))
      (node (ref "K10") (pin "1") (pinfunction "1_1") (pintype "passive"))
      (node (ref "K11") (pin "2") (pintype "passive"))
      (node (ref "K12") (pin "2") (pintype "passive"))
      (node (ref "K13") (pin "2") (pintype "passive"))
      (node (ref "K14") (pin "2") (pintype "passive"))
      (node (ref "K15") (pin "2") (pintype "passive"))
      (node (ref "K2") (pin "1") (pinfunction "1_1") (pintype "passive"))
      (node (ref "K3") (pin "1") (pinfunction "1_1") (pintype "passive"))
      (node (ref "K4") (pin "1") (pinfunction "1_1") (pintype "passive"))
      (node (ref "K5") (pin "1") (pinfunction "1_1") (pintype "passive"))
      (node (ref "K6") (pin "1") (pinfunction "1_1") (pintype "passive"))
      (node (ref "K7") (pin "1") (pinfunction "1_1") (pintype "passive"))
      (node (ref "K8") (pin "1") (pinfunction "1_1") (pintype "passive"))
      (node (ref "K9") (pin "1") (pinfunction "1_1") (pintype "passive"))
      (node (ref "U2") (pin "5") (pinfunction "V+_5") (pintype "passive"))
      (node (ref "U23") (pin "8") (pinfunction "V+_8") (pintype "passive"))
      (node (ref "U3") (pin "8") (pinfunction "V+_8") (pintype "passive"))
      (node (ref "U4") (pin "8") (pinfunction "V+_8") (pintype "passive"))
      (node (ref "U6") (pin "8") (pinfunction "Vs+_8") (pintype "passive"))
      (node (ref "U7") (pin "8") (pinfunction "Vs+_8") (pintype "passive"))
    )
    (net (code "2") (name "-5V") (class "Default")
      (node (ref "C121") (pin "2") (pinfunction "2_2") (pintype "passive"))
      (node (ref "C14") (pin "2") (pinfunction "2_2") (pintype "passive"))
      (node (ref "C95") (pin "2") (pinfunction "2_2") (pintype "passive"))
      (node (ref "U13") (pin "4") (pinfunction "V-_4") (pintype "passive"))
      (node (ref "U17") (pin "3") (pinfunction "-Vs_3") (pintype "passive"))
      (node (ref "U18") (pin "3") (pinfunction "-Vs_3") (pintype "passive"))
    )
    (net (code "3") (name "-15V") (class "Default")
      (node (ref "C101") (pin "2") (pinfunction "2_2") (pintype "passive"))
      (node (ref "C102") (pin "2") (pinfunction "2_2") (pintype "passive"))
      (node (ref "C105") (pin "2") (pinfunction "2_2") (pintype "passive"))
      (node (ref "C106") (pin "2") (pinfunction "2_2") (pintype "passive"))
      (node (ref "C152") (pin "2") (pinfunction "2_2") (pintype "passive"))
      (node (ref "C153") (pin "2") (pinfunction "2_2") (pintype "passive"))
      (node (ref "C17") (pin "2") (pinfunction "2_2") (pintype "passive"))
      (node (ref "C18") (pin "2") (pinfunction "2_2") (pintype "passive"))
      (node (ref "C41") (pin "2") (pinfunction "2_2") (pintype "passive"))
      (node (ref "C42") (pin "2") (pinfunction "2_2") (pintype "passive"))
      (node (ref "C45") (pin "2") (pinfunction "2_2") (pintype "passive"))
      (node (ref "C46") (pin "2") (pinfunction "2_2") (pintype "passive"))
      (node (ref "R27") (pin "1") (pinfunction "1_1") (pintype "passive"))
      (node (ref "U2") (pin "3") (pinfunction "V-_3") (pintype "passive"))
      (node (ref "U23") (pin "4") (pinfunction "V-_4") (pintype "passive"))
      (node (ref "U3") (pin "4") (pinfunction "V-_4") (pintype "passive"))
      (node (ref "U4") (pin "4") (pinfunction "V-_4") (pintype "passive"))
      (node (ref "U6") (pin "5") (pinfunction "Vs-_5") (pintype "passive"))
      (node (ref "U7") (pin "5") (pinfunction "Vs-_5") (pintype "passive"))
    )
    (net (code "4") (name "/1.25V") (class "Default")
      (node (ref "U13") (pin "6") (pinfunction "-IN_B_6") (pintype "passive"))
      (node (ref "U13") (pin "7") (pinfunction "Out_B_7") (pintype "passive"))
      (node (ref "U17") (pin "9") (pinfunction "REF_9") (pintype "passive"))
      (node (ref "U18") (pin "9") (pinfunction "REF_9") (pintype "passive"))
    )
    (net (code "5") (name "/2.5V") (class "Default")
      (node (ref "C82") (pin "1") (pinfunction "1_1") (pintype "passive"))
      (node (ref "C83") (pin "1") (pinfunction "1_1") (pintype "passive"))
      (node (ref "R22") (pin "1") (pinfunction "1_1") (pintype "passive"))
      (node (ref "R61") (pin "1") (pinfunction "1_1") (pintype "passive"))
      (node (ref "U10") (pin "1") (pinfunction "REF_1") (pintype "passive"))
      (node (ref "U10") (pin "2") (pinfunction "VDD_2") (pintype "passive"))
      (node (ref "U11") (pin "1") (pinfunction "REF_1") (pintype "passive"))
      (node (ref "U11") (pin "2") (pinfunction "VDD_2") (pintype "passive"))
      (node (ref "U13") (pin "1") (pinfunction "Out_A_1") (pintype "passive"))
      (node (ref "U13") (pin "2") (pinfunction "-IN_A_2") (pintype "input"))
    )
    (net (code "6") (name "/ADC1_CNV") (class "Default")
      (node (ref "U1") (pin "38") (pinfunction "PC7_38") (pintype "bidirectional"))
      (node (ref "U10") (pin "6") (pinfunction "CNV_6") (pintype "passive"))
    )
    (net (code "7") (name "/ADC1_SCK") (class "Default")
      (node (ref "U1") (pin "36") (pinfunction "PB15_36") (pintype "bidirectional"))
      (node (ref "U10") (pin "8") (pinfunction "SCK_8") (pintype "passive"))
    )
    (net (code "8") (name "/ADC1_SDI") (class "Default")
      (node (ref "U1") (pin "35") (pinfunction "PB14_35") (pintype "bidirectional"))
      (node (ref "U10") (pin "9") (pinfunction "SDI_9") (pintype "passive"))
    )
    (net (code "9") (name "/ADC1_SDO") (class "Default")
      (node (ref "U1") (pin "37") (pinfunction "PC6_37") (pintype "bidirectional"))
      (node (ref "U10") (pin "7") (pinfunction "SDO_7") (pintype "passive"))
    )
    (net (code "10") (name "/ADC2_CNV") (class "Default")
      (node (ref "U1") (pin "23") (pinfunction "PA7_23") (pintype "bidirectional"))
      (node (ref "U11") (pin "6") (pinfunction "CNV_6") (pintype "passive"))
    )
    (net (code "11") (name "/ADC2_SCK") (class "Default")
      (node (ref "U1") (pin "21") (pinfunction "PA5_21") (pintype "bidirectional"))
      (node (ref "U11") (pin "8") (pinfunction "SCK_8") (pintype "passive"))
    )
    (net (code "12") (name "/ADC2_SDI") (class "Default")
      (node (ref "U1") (pin "20") (pinfunction "PA4_20") (pintype "bidirectional"))
      (node (ref "U11") (pin "9") (pinfunction "SDI_9") (pintype "passive"))
    )
    (net (code "13") (name "/ADC2_SDO") (class "Default")
      (node (ref "U1") (pin "22") (pinfunction "PA6_22") (pintype "bidirectional"))
      (node (ref "U11") (pin "7") (pinfunction "SDO_7") (pintype "passive"))
    )
    (net (code "14") (name "/Ctrl1") (class "Default")
      (node (ref "Q1") (pin "1") (pinfunction "Gate_1") (pintype "passive"))
      (node (ref "U1") (pin "8") (pinfunction "PC0_8") (pintype "bidirectional"))
    )
    (net (code "15") (name "/Ctrl2") (class "Default")
      (node (ref "Q2") (pin "1") (pinfunction "Gate_1") (pintype "passive"))
      (node (ref "U1") (pin "9") (pinfunction "PC1_9") (pintype "bidirectional"))
    )
    (net (code "16") (name "/Ctrl3") (class "Default")
      (node (ref "Q3") (pin "1") (pinfunction "Gate_1") (pintype "passive"))
      (node (ref "U1") (pin "10") (pinfunction "PC2_10") (pintype "bidirectional"))
    )
    (net (code "17") (name "/Ctrl4") (class "Default")
      (node (ref "Q4") (pin "1") (pinfunction "Gate_1") (pintype "passive"))
      (node (ref "U1") (pin "11") (pinfunction "PC3_11") (pintype "bidirectional"))
    )
    (net (code "18") (name "/Ctrl5") (class "Default")
      (node (ref "Q5") (pin "1") (pinfunction "Gate_1") (pintype "passive"))
      (node (ref "U1") (pin "24") (pinfunction "PC4_24") (pintype "bidirectional"))
    )
    (net (code "19") (name "/Ctrl6") (class "Default")
      (node (ref "Q6") (pin "1") (pinfunction "Gate_1") (pintype "passive"))
      (node (ref "U1") (pin "25") (pinfunction "PC5_25") (pintype "bidirectional"))
    )
    (net (code "20") (name "/Ctrl7") (class "Default")
      (node (ref "Q7") (pin "1") (pinfunction "Gate_1") (pintype "passive"))
      (node (ref "U1") (pin "26") (pinfunction "PB0_26") (pintype "bidirectional"))
    )
    (net (code "21") (name "/Ctrl8") (class "Default")
      (node (ref "Q8") (pin "1") (pinfunction "Gate_1") (pintype "passive"))
      (node (ref "U1") (pin "27") (pinfunction "PB1_27") (pintype "bidirectional"))
    )
    (net (code "22") (name "/Ctrl9") (class "Default")
      (node (ref "Q9") (pin "1") (pinfunction "Gate_1") (pintype "passive"))
      (node (ref "U1") (pin "28") (pinfunction "PB2/BOOT1_28") (pintype "bidirectional"))
    )
    (net (code "23") (name "/Ctrl10") (class "Default")
      (node (ref "Q10") (pin "1") (pinfunction "Gate_1") (pintype "passive"))
      (node (ref "U1") (pin "33") (pinfunction "PB12_33") (pintype "bidirectional"))
    )
    (net (code "24") (name "/Ctrl11") (class "Default")
      (node (ref "Q11") (pin "1") (pinfunction "Gate_1") (pintype "passive"))
      (node (ref "U1") (pin "55") (pinfunction "PB3/JTDO_55") (pintype "bidirectional"))
    )
    (net (code "25") (name "/Ctrl12") (class "Default")
      (node (ref "Q12") (pin "1") (pinfunction "Gate_1") (pintype "passive"))
      (node (ref "U1") (pin "56") (pinfunction "PB4/JNTRST_56") (pintype "bidirectional"))
    )
    (net (code "26") (name "/Ctrl13") (class "Default")
      (node (ref "Q13") (pin "1") (pinfunction "Gate_1") (pintype "passive"))
      (node (ref "U1") (pin "52") (pinfunction "PC11_52") (pintype "bidirectional"))
    )
    (net (code "27") (name "/Ctrl14") (class "Default")
      (node (ref "Q14") (pin "1") (pinfunction "Gate_1") (pintype "passive"))
      (node (ref "U1") (pin "51") (pinfunction "PC10_51") (pintype "bidirectional"))
    )
    (net (code "28") (name "/Ctrl15") (class "Default")
      (node (ref "Q15") (pin "1") (pinfunction "Gate_1") (pintype "passive"))
      (node (ref "U1") (pin "57") (pinfunction "PB5_57") (pintype "bidirectional"))
    )
    (net (code "29") (name "/D1") (class "Default")
      (node (ref "K1") (pin "8") (pinfunction "8_8") (pintype "passive"))
      (node (ref "Q1") (pin "3") (pinfunction "Drain_3") (pintype "passive"))
    )
    (net (code "30") (name "/D2") (class "Default")
      (node (ref "K2") (pin "8") (pinfunction "8_8") (pintype "passive"))
      (node (ref "Q2") (pin "3") (pinfunction "Drain_3") (pintype "passive"))
    )
    (net (code "31") (name "/D3") (class "Default")
      (node (ref "K3") (pin "8") (pinfunction "8_8") (pintype "passive"))
      (node (ref "Q3") (pin "3") (pinfunction "Drain_3") (pintype "passive"))
    )
    (net (code "32") (name "/D4") (class "Default")
      (node (ref "K4") (pin "8") (pinfunction "8_8") (pintype "passive"))
      (node (ref "Q4") (pin "3") (pinfunction "Drain_3") (pintype "passive"))
    )
    (net (code "33") (name "/D5") (class "Default")
      (node (ref "K5") (pin "8") (pinfunction "8_8") (pintype "passive"))
      (node (ref "Q5") (pin "3") (pinfunction "Drain_3") (pintype "passive"))
    )
    (net (code "34") (name "/D6") (class "Default")
      (node (ref "K6") (pin "8") (pinfunction "8_8") (pintype "passive"))
      (node (ref "Q6") (pin "3") (pinfunction "Drain_3") (pintype "passive"))
    )
    (net (code "35") (name "/D7") (class "Default")
      (node (ref "K7") (pin "8") (pinfunction "8_8") (pintype "passive"))
      (node (ref "Q7") (pin "3") (pinfunction "Drain_3") (pintype "passive"))
    )
    (net (code "36") (name "/D8") (class "Default")
      (node (ref "K8") (pin "8") (pinfunction "8_8") (pintype "passive"))
      (node (ref "Q8") (pin "3") (pinfunction "Drain_3") (pintype "passive"))
    )
    (net (code "37") (name "/D9") (class "Default")
      (node (ref "K9") (pin "8") (pinfunction "8_8") (pintype "passive"))
      (node (ref "Q9") (pin "3") (pinfunction "Drain_3") (pintype "passive"))
    )
    (net (code "38") (name "/D10") (class "Default")
      (node (ref "K10") (pin "8") (pinfunction "8_8") (pintype "passive"))
      (node (ref "Q10") (pin "3") (pinfunction "Drain_3") (pintype "passive"))
    )
    (net (code "39") (name "/D11") (class "Default")
      (node (ref "K11") (pin "5") (pintype "passive"))
      (node (ref "Q11") (pin "3") (pinfunction "Drain_3") (pintype "passive"))
    )
    (net (code "40") (name "/D12") (class "Default")
      (node (ref "K12") (pin "5") (pintype "passive"))
      (node (ref "Q12") (pin "3") (pinfunction "Drain_3") (pintype "passive"))
    )
    (net (code "41") (name "/D13") (class "Default")
      (node (ref "K13") (pin "5") (pintype "passive"))
      (node (ref "Q13") (pin "3") (pinfunction "Drain_3") (pintype "passive"))
    )
    (net (code "42") (name "/D14") (class "Default")
      (node (ref "K14") (pin "5") (pintype "passive"))
      (node (ref "Q14") (pin "3") (pinfunction "Drain_3") (pintype "passive"))
    )
    (net (code "43") (name "/D15") (class "Default")
      (node (ref "K15") (pin "5") (pintype "passive"))
      (node (ref "Q15") (pin "3") (pinfunction "Drain_3") (pintype "passive"))
    )
    (net (code "44") (name "/DAC1_FSYNC") (class "Default")
      (node (ref "U1") (pin "41") (pinfunction "PA8_41") (pintype "bidirectional"))
      (node (ref "U14") (pin "13") (pinfunction "/SYNC_13") (pintype "passive"))
    )
    (net (code "45") (name "/DAC1_RESET") (class "Default")
      (node (ref "U1") (pin "14") (pinfunction "PA0-WKUP_14") (pintype "bidirectional"))
      (node (ref "U14") (pin "15") (pinfunction "/RESET_15") (pintype "passive"))
    )
    (net (code "46") (name "/DAC1_SCLK") (class "Default")
      (node (ref "U1") (pin "40") (pinfunction "PC9_40") (pintype "bidirectional"))
      (node (ref "U14") (pin "12") (pinfunction "SCLK_12") (pintype "passive"))
    )
    (net (code "47") (name "/DAC1_SDATA") (class "Default")
      (node (ref "U1") (pin "15") (pinfunction "PA1_15") (pintype "bidirectional"))
      (node (ref "U14") (pin "14") (pinfunction "SDIN_14") (pintype "passive"))
    )
    (net (code "48") (name "/DUT_VOLTAGE") (class "Default")
      (node (ref "K12") (pin "1") (pintype "passive"))
      (node (ref "R51") (pin "2") (pinfunction "2_2") (pintype "passive"))
      (node (ref "T2") (pin "1") (pinfunction "1_1") (pintype "passive"))
      (node (ref "U7") (pin "7") (pinfunction "Vout_7") (pintype "passive"))
    )
    (net (code "49") (name "/FB_R_T1") (class "Default")
      (node (ref "C70") (pin "1") (pinfunction "1_1") (pintype "passive"))
      (node (ref "C71") (pin "1") (pinfunction "1_1") (pintype "passive"))
      (node (ref "C72") (pin "1") (pinfunction "1_1") (pintype "passive"))
      (node (ref "C73") (pin "1") (pinfunction "1_1") (pintype "passive"))
      (node (ref "C74") (pin "1") (pinfunction "1_1") (pintype "passive"))
      (node (ref "C75") (pin "1") (pinfunction "1_1") (pintype "passive"))
      (node (ref "C76") (pin "1") (pinfunction "1_1") (pintype "passive"))
      (node (ref "C77") (pin "1") (pinfunction "1_1") (pintype "passive"))
      (node (ref "C78") (pin "1") (pinfunction "1_1") (pintype "passive"))
      (node (ref "C79") (pin "1") (pinfunction "1_1") (pintype "passive"))
      (node (ref "K15") (pin "6") (pintype "passive"))
      (node (ref "R19") (pin "2") (pinfunction "2_2") (pintype "passive"))
      (node (ref "R31") (pin "1") (pinfunction "1_1") (pintype "passive"))
      (node (ref "R32") (pin "1") (pinfunction "1_1") (pintype "passive"))
      (node (ref "R33") (pin "1") (pinfunction "1_1") (pintype "passive"))
      (node (ref "R34") (pin "1") (pinfunction "1_1") (pintype "passive"))
      (node (ref "R35") (pin "1") (pinfunction "1_1") (pintype "passive"))
      (node (ref "R36") (pin "1") (pinfunction "1_1") (pintype "passive"))
      (node (ref "R37") (pin "1") (pinfunction "1_1") (pintype "passive"))
      (node (ref "R38") (pin "1") (pinfunction "1_1") (pintype "passive"))
      (node (ref "R39") (pin "1") (pinfunction "1_1") (pintype "passive"))
      (node (ref "R40") (pin "1") (pinfunction "1_1") (pintype "passive"))
    )
    (net (code "50") (name "/FB_R_T2") (class "Default")
      (node (ref "K1") (pin "5") (pinfunction "5_5") (pintype "passive"))
      (node (ref "K10") (pin "5") (pinfunction "5_5") (pintype "passive"))
      (node (ref "K2") (pin "5") (pinfunction "5_5") (pintype "passive"))
      (node (ref "K3") (pin "5") (pinfunction "5_5") (pintype "passive"))
      (node (ref "K4") (pin "5") (pinfunction "5_5") (pintype "passive"))
      (node (ref "K5") (pin "5") (pinfunction "5_5") (pintype "passive"))
      (node (ref "K6") (pin "5") (pinfunction "5_5") (pintype "passive"))
      (node (ref "K7") (pin "5") (pinfunction "5_5") (pintype "passive"))
      (node (ref "K8") (pin "5") (pinfunction "5_5") (pintype "passive"))
      (node (ref "K9") (pin "5") (pinfunction "5_5") (pintype "passive"))
      (node (ref "R21") (pin "2") (pinfunction "2_2") (pintype "passive"))
      (node (ref "U2") (pin "4") (pinfunction "Vout_4") (pintype "passive"))
    )
    (net (code "51") (name "/FH_Out") (class "Default")
      (node (ref "FORCE_H") (pin "1") (pinfunction "X_1") (pintype "passive"))
      (node (ref "K15") (pin "4") (pintype "passive"))
      (node (ref "R76") (pin "1") (pinfunction "1_1") (pintype "passive"))
      (node (ref "U4") (pin "5") (pinfunction "+IN_B_5") (pintype "passive"))
    )
    (net (code "52") (name "/LED0") (class "Default")
      (node (ref "R68") (pin "2") (pinfunction "2_2") (pintype "passive"))
      (node (ref "U1") (pin "53") (pinfunction "PC12_53") (pintype "bidirectional"))
    )
    (net (code "53") (name "/LED1") (class "Default")
      (node (ref "R69") (pin "2") (pinfunction "2_2") (pintype "passive"))
      (node (ref "U1") (pin "54") (pinfunction "PD2_54") (pintype "bidirectional"))
    )
    (net (code "54") (name "/NULL") (class "Default")
      (node (ref "C47") (pin "1") (pinfunction "1_1") (pintype "passive"))
      (node (ref "U14") (pin "7") (pinfunction "VoutB_7") (pintype "passive"))
    )
    (net (code "55") (name "/PGA1_A0") (class "Default")
      (node (ref "U1") (pin "61") (pinfunction "PB8_61") (pintype "bidirectional"))
      (node (ref "U17") (pin "4") (pinfunction "A0_4") (pintype "passive"))
    )
    (net (code "56") (name "/PGA1_A1") (class "Default")
      (node (ref "U1") (pin "62") (pinfunction "PB9_62") (pintype "bidirectional"))
      (node (ref "U17") (pin "5") (pinfunction "A1_5") (pintype "passive"))
    )
    (net (code "57") (name "/PGA1_WR") (class "Default")
      (node (ref "U1") (pin "59") (pinfunction "PB7_59") (pintype "bidirectional"))
      (node (ref "U17") (pin "6") (pinfunction "/WR_6") (pintype "passive"))
    )
    (net (code "58") (name "/PGA2_A0") (class "Default")
      (node (ref "U1") (pin "50") (pinfunction "PA15/JTDI_50") (pintype "bidirectional"))
      (node (ref "U18") (pin "4") (pinfunction "A0_4") (pintype "passive"))
    )
    (net (code "59") (name "/PGA2_A1") (class "Default")
      (node (ref "U1") (pin "34") (pinfunction "PB13_34") (pintype "bidirectional"))
      (node (ref "U18") (pin "5") (pinfunction "A1_5") (pintype "passive"))
    )
    (net (code "60") (name "/PGA2_WR") (class "Default")
      (node (ref "U1") (pin "2") (pinfunction "PC13-TAMPER-RTC_2") (pintype "bidirectional"))
      (node (ref "U18") (pin "6") (pinfunction "/WR_6") (pintype "passive"))
    )
    (net (code "61") (name "/RS485_RE") (class "Default")
      (node (ref "U1") (pin "58") (pinfunction "PB6_58") (pintype "bidirectional"))
      (node (ref "U44") (pin "2") (pinfunction "/RE_2") (pintype "passive"))
      (node (ref "U44") (pin "3") (pinfunction "DE_3") (pintype "passive"))
    )
    (net (code "62") (name "/RS485_RE2") (class "Default")
      (node (ref "U1") (pin "39") (pinfunction "PC8_39") (pintype "bidirectional"))
      (node (ref "U45") (pin "2") (pinfunction "/RE_2") (pintype "passive"))
      (node (ref "U45") (pin "3") (pinfunction "DE_3") (pintype "passive"))
    )
    (net (code "63") (name "/R_VOLTAGE") (class "Default")
      (node (ref "K12") (pin "6") (pintype "passive"))
      (node (ref "R49") (pin "2") (pinfunction "2_2") (pintype "passive"))
      (node (ref "T1") (pin "1") (pinfunction "1_1") (pintype "passive"))
      (node (ref "U6") (pin "7") (pinfunction "Vout_7") (pintype "passive"))
    )
    (net (code "64") (name "/Rg1+") (class "Default")
      (node (ref "K13") (pin "6") (pintype "passive"))
      (node (ref "U6") (pin "2") (pinfunction "Rg_2") (pintype "passive"))
    )
    (net (code "65") (name "/Rg1-") (class "Default")
      (node (ref "R44") (pin "2") (pinfunction "2_2") (pintype "passive"))
      (node (ref "U6") (pin "3") (pinfunction "Rg_3") (pintype "passive"))
    )
    (net (code "66") (name "/Rg2+") (class "Default")
      (node (ref "K14") (pin "6") (pintype "passive"))
      (node (ref "U7") (pin "2") (pinfunction "Rg_2") (pintype "passive"))
    )
    (net (code "67") (name "/Rg2-") (class "Default")
      (node (ref "R45") (pin "2") (pinfunction "2_2") (pintype "passive"))
      (node (ref "U7") (pin "3") (pinfunction "Rg_3") (pintype "passive"))
    )
    (net (code "68") (name "/SENSE_H") (class "Default")
      (node (ref "R14") (pin "1") (pinfunction "1_1") (pintype "passive"))
      (node (ref "R76") (pin "2") (pinfunction "2_2") (pintype "passive"))
      (node (ref "SENSE_H") (pin "1") (pinfunction "X_1") (pintype "passive"))
    )
    (net (code "69") (name "/SENSE_L") (class "Default")
      (node (ref "R12") (pin "1") (pinfunction "1_1") (pintype "passive"))
      (node (ref "R75") (pin "1") (pinfunction "1_1") (pintype "passive"))
      (node (ref "SENSE_L") (pin "1") (pinfunction "X_1") (pintype "passive"))
    )
    (net (code "70") (name "/SWCLK") (class "Default")
      (node (ref "DL") (pin "2") (pinfunction "D-_2") (pintype "passive"))
      (node (ref "U1") (pin "49") (pinfunction "PA14/JTCK/SWCLK_49") (pintype "bidirectional"))
    )
    (net (code "71") (name "/SWDIO") (class "Default")
      (node (ref "DL") (pin "3") (pinfunction "D+_3") (pintype "passive"))
      (node (ref "DL") (pin "4") (pinfunction "ID_4") (pintype "passive"))
      (node (ref "U1") (pin "46") (pinfunction "PA13/JTMS/SWDIO_46") (pintype "bidirectional"))
    )
    (net (code "72") (name "/SigIn") (class "Default")
      (node (ref "C154") (pin "2") (pinfunction "2_2") (pintype "passive"))
      (node (ref "R25") (pin "2") (pinfunction "2_2") (pintype "passive"))
      (node (ref "T3") (pin "1") (pinfunction "1_1") (pintype "passive"))
      (node (ref "U23") (pin "1") (pinfunction "Out_A_1") (pintype "passive"))
      (node (ref "U3") (pin "3") (pinfunction "+IN_A_3") (pintype "input"))
    )
    (net (code "73") (name "/SigOut") (class "Default")
      (node (ref "C48") (pin "1") (pinfunction "1_1") (pintype "passive"))
      (node (ref "R24") (pin "1") (pinfunction "1_1") (pintype "passive"))
      (node (ref "U14") (pin "3") (pinfunction "VoutA_3") (pintype "passive"))
    )
    (net (code "74") (name "/UART3_RX") (class "Default")
      (node (ref "LCD") (pin "5") (pinfunction "5_5") (pintype "passive"))
      (node (ref "U1") (pin "30") (pinfunction "PB11_30") (pintype "bidirectional"))
    )
    (net (code "75") (name "/UART3_TX") (class "Default")
      (node (ref "LCD") (pin "3") (pinfunction "3_3") (pintype "passive"))
      (node (ref "LCD") (pin "4") (pinfunction "4_4") (pintype "passive"))
      (node (ref "U1") (pin "29") (pinfunction "PB10_29") (pintype "bidirectional"))
    )
    (net (code "76") (name "/USART1_RX") (class "Default")
      (node (ref "U1") (pin "43") (pinfunction "PA10_43") (pintype "bidirectional"))
      (node (ref "U44") (pin "1") (pinfunction "RO_1") (pintype "passive"))
    )
    (net (code "77") (name "/USART1_TX") (class "Default")
      (node (ref "U1") (pin "42") (pinfunction "PA9_42") (pintype "bidirectional"))
      (node (ref "U44") (pin "4") (pinfunction "DI_4") (pintype "passive"))
    )
    (net (code "78") (name "/USART2_RX") (class "Default")
      (node (ref "U1") (pin "17") (pinfunction "PA3_17") (pintype "bidirectional"))
      (node (ref "U45") (pin "1") (pinfunction "RO_1") (pintype "passive"))
    )
    (net (code "79") (name "/USART2_TX") (class "Default")
      (node (ref "U1") (pin "16") (pinfunction "PA2_16") (pintype "bidirectional"))
      (node (ref "U45") (pin "4") (pinfunction "DI_4") (pintype "passive"))
    )
    (net (code "80") (name "/USB_DM") (class "Default")
      (node (ref "R43") (pin "2") (pinfunction "2_2") (pintype "passive"))
      (node (ref "U1") (pin "44") (pinfunction "PA11_44") (pintype "bidirectional"))
    )
    (net (code "81") (name "/USB_DP") (class "Default")
      (node (ref "R41") (pin "2") (pinfunction "2_2") (pintype "passive"))
      (node (ref "R42") (pin "2") (pinfunction "2_2") (pintype "passive"))
      (node (ref "U1") (pin "45") (pinfunction "PA12_45") (pintype "bidirectional"))
    )
    (net (code "82") (name "5V") (class "Default")
      (node (ref "C10") (pin "1") (pinfunction "1_1") (pintype "passive"))
      (node (ref "C120") (pin "2") (pinfunction "2_2") (pintype "passive"))
      (node (ref "C13") (pin "2") (pinfunction "2_2") (pintype "passive"))
      (node (ref "C156") (pin "1") (pinfunction "1_1") (pintype "passive"))
      (node (ref "C9") (pin "2") (pinfunction "2_2") (pintype "passive"))
      (node (ref "C93") (pin "1") (pinfunction "1_1") (pintype "passive"))
      (node (ref "C94") (pin "2") (pinfunction "2_2") (pintype "passive"))
      (node (ref "U12") (pin "2") (pinfunction "Vin_2") (pintype "passive"))
      (node (ref "U13") (pin "8") (pinfunction "V+_8") (pintype "passive"))
      (node (ref "U14") (pin "5") (pinfunction "Vdd_5") (pintype "passive"))
      (node (ref "U17") (pin "8") (pinfunction "+Vs_8") (pintype "passive"))
      (node (ref "U18") (pin "8") (pinfunction "+Vs_8") (pintype "passive"))
    )
    (net (code "83") (name "AGND") (class "Default")
      (node (ref "C10") (pin "2") (pinfunction "2_2") (pintype "passive"))
      (node (ref "C100") (pin "2") (pinfunction "2_2") (pintype "passive"))
      (node (ref "C101") (pin "1") (pinfunction "1_1") (pintype "passive"))
      (node (ref "C102") (pin "1") (pinfunction "1_1") (pintype "passive"))
      (node (ref "C103") (pin "1") (pinfunction "1_1") (pintype "passive"))
      (node (ref "C104") (pin "2") (pinfunction "2_2") (pintype "passive"))
      (node (ref "C105") (pin "1") (pinfunction "1_1") (pintype "passive"))
      (node (ref "C106") (pin "1") (pinfunction "1_1") (pintype "passive"))
      (node (ref "C120") (pin "1") (pinfunction "1_1") (pintype "passive"))
      (node (ref "C121") (pin "1") (pinfunction "1_1") (pintype "passive"))
      (node (ref "C13") (pin "1") (pinfunction "1_1") (pintype "passive"))
      (node (ref "C14") (pin "1") (pinfunction "1_1") (pintype "passive"))
      (node (ref "C15") (pin "1") (pinfunction "1_1") (pintype "passive"))
      (node (ref "C150") (pin "1") (pinfunction "1_1") (pintype "passive"))
      (node (ref "C151") (pin "2") (pinfunction "2_2") (pintype "passive"))
      (node (ref "C152") (pin "1") (pinfunction "1_1") (pintype "passive"))
      (node (ref "C153") (pin "1") (pinfunction "1_1") (pintype "passive"))
      (node (ref "C156") (pin "2") (pinfunction "2_2") (pintype "passive"))
      (node (ref "C16") (pin "2") (pinfunction "2_2") (pintype "passive"))
      (node (ref "C17") (pin "1") (pinfunction "1_1") (pintype "passive"))
      (node (ref "C18") (pin "1") (pinfunction "1_1") (pintype "passive"))
      (node (ref "C19") (pin "1") (pinfunction "1_1") (pintype "passive"))
      (node (ref "C20") (pin "1") (pinfunction "1_1") (pintype "passive"))
      (node (ref "C21") (pin "2") (pinfunction "2_2") (pintype "passive"))
      (node (ref "C31") (pin "1") (pinfunction "1_1") (pintype "passive"))
      (node (ref "C32") (pin "2") (pinfunction "2_2") (pintype "passive"))
      (node (ref "C33") (pin "1") (pinfunction "1_1") (pintype "passive"))
      (node (ref "C35") (pin "2") (pinfunction "2_2") (pintype "passive"))
      (node (ref "C37") (pin "1") (pinfunction "1_1") (pintype "passive"))
      (node (ref "C38") (pin "2") (pinfunction "2_2") (pintype "passive"))
      (node (ref "C39") (pin "1") (pinfunction "1_1") (pintype "passive"))
      (node (ref "C40") (pin "2") (pinfunction "2_2") (pintype "passive"))
      (node (ref "C41") (pin "1") (pinfunction "1_1") (pintype "passive"))
      (node (ref "C42") (pin "1") (pinfunction "1_1") (pintype "passive"))
      (node (ref "C43") (pin "1") (pinfunction "1_1") (pintype "passive"))
      (node (ref "C44") (pin "2") (pinfunction "2_2") (pintype "passive"))
      (node (ref "C45") (pin "1") (pinfunction "1_1") (pintype "passive"))
      (node (ref "C46") (pin "1") (pinfunction "1_1") (pintype "passive"))
      (node (ref "C47") (pin "2") (pinfunction "2_2") (pintype "passive"))
      (node (ref "C48") (pin "2") (pinfunction "2_2") (pintype "passive"))
      (node (ref "C49") (pin "2") (pinfunction "2_2") (pintype "passive"))
      (node (ref "C80") (pin "2") (pinfunction "2_2") (pintype "passive"))
      (node (ref "C82") (pin "2") (pinfunction "2_2") (pintype "passive"))
      (node (ref "C83") (pin "2") (pinfunction "2_2") (pintype "passive"))
      (node (ref "C84") (pin "1") (pinfunction "1_1") (pintype "passive"))
      (node (ref "C9") (pin "1") (pinfunction "1_1") (pintype "passive"))
      (node (ref "C90") (pin "1") (pinfunction "1_1") (pintype "passive"))
      (node (ref "C93") (pin "2") (pinfunction "2_2") (pintype "passive"))
      (node (ref "C94") (pin "1") (pinfunction "1_1") (pintype "passive"))
      (node (ref "C95") (pin "1") (pinfunction "1_1") (pintype "passive"))
      (node (ref "FORCE_L") (pin "1") (pinfunction "X_1") (pintype "passive"))
      (node (ref "FORCE_L") (pin "2") (pinfunction "Y_2") (pintype "passive"))
      (node (ref "GUARD") (pin "2") (pinfunction "Y_2") (pintype "passive"))
      (node (ref "K15") (pin "1") (pintype "passive"))
      (node (ref "L3") (pin "1") (pinfunction "1_1") (pintype "passive"))
      (node (ref "Q1") (pin "2") (pinfunction "Source_2") (pintype "passive"))
      (node (ref "Q10") (pin "2") (pinfunction "Source_2") (pintype "passive"))
      (node (ref "Q11") (pin "2") (pinfunction "Source_2") (pintype "passive"))
      (node (ref "Q12") (pin "2") (pinfunction "Source_2") (pintype "passive"))
      (node (ref "Q13") (pin "2") (pinfunction "Source_2") (pintype "passive"))
      (node (ref "Q14") (pin "2") (pinfunction "Source_2") (pintype "passive"))
      (node (ref "Q15") (pin "2") (pinfunction "Source_2") (pintype "passive"))
      (node (ref "Q2") (pin "2") (pinfunction "Source_2") (pintype "passive"))
      (node (ref "Q3") (pin "2") (pinfunction "Source_2") (pintype "passive"))
      (node (ref "Q4") (pin "2") (pinfunction "Source_2") (pintype "passive"))
      (node (ref "Q5") (pin "2") (pinfunction "Source_2") (pintype "passive"))
      (node (ref "Q6") (pin "2") (pinfunction "Source_2") (pintype "passive"))
      (node (ref "Q7") (pin "2") (pinfunction "Source_2") (pintype "passive"))
      (node (ref "Q8") (pin "2") (pinfunction "Source_2") (pintype "passive"))
      (node (ref "Q9") (pin "2") (pinfunction "Source_2") (pintype "passive"))
      (node (ref "R17") (pin "2") (pinfunction "2_2") (pintype "passive"))
      (node (ref "R23") (pin "1") (pinfunction "1_1") (pintype "passive"))
      (node (ref "R50") (pin "1") (pinfunction "1_1") (pintype "passive"))
      (node (ref "R52") (pin "1") (pinfunction "1_1") (pintype "passive"))
      (node (ref "R62") (pin "2") (pinfunction "2_2") (pintype "passive"))
      (node (ref "R75") (pin "2") (pinfunction "2_2") (pintype "passive"))
      (node (ref "SENSE_L") (pin "2") (pinfunction "Y_2") (pintype "passive"))
      (node (ref "T5") (pin "1") (pinfunction "1_1") (pintype "passive"))
      (node (ref "U10") (pin "4") (pinfunction "IN-_4") (pintype "passive"))
      (node (ref "U10") (pin "5") (pinfunction "GND_5") (pintype "passive"))
      (node (ref "U11") (pin "4") (pinfunction "IN-_4") (pintype "passive"))
      (node (ref "U11") (pin "5") (pinfunction "GND_5") (pintype "passive"))
      (node (ref "U12") (pin "4") (pinfunction "GND_4") (pintype "passive"))
      (node (ref "U14") (pin "16") (pinfunction "RSTSEL_16") (pintype "passive"))
      (node (ref "U14") (pin "4") (pinfunction "GND_4") (pintype "passive"))
      (node (ref "U14") (pin "9") (pinfunction "/LDAC_9") (pintype "passive"))
      (node (ref "U17") (pin "1") (pinfunction "-IN_1") (pintype "passive"))
      (node (ref "U17") (pin "2") (pinfunction "DGND_2") (pintype "passive"))
      (node (ref "U18") (pin "1") (pinfunction "-IN_1") (pintype "passive"))
      (node (ref "U18") (pin "2") (pinfunction "DGND_2") (pintype "passive"))
      (node (ref "U23") (pin "5") (pinfunction "+IN_B_5") (pintype "passive"))
      (node (ref "U6") (pin "6") (pinfunction "Ref_6") (pintype "passive"))
      (node (ref "U7") (pin "6") (pinfunction "Ref_6") (pintype "passive"))
    )
    (net (code "84") (name "D3V3") (class "Default")
      (node (ref "C1") (pin "2") (pinfunction "2_2") (pintype "passive"))
      (node (ref "C108") (pin "2") (pinfunction "2_2") (pintype "passive"))
      (node (ref "C2") (pin "2") (pinfunction "2_2") (pintype "passive"))
      (node (ref "C22") (pin "2") (pinfunction "2_2") (pintype "passive"))
      (node (ref "C29") (pin "2") (pinfunction "2_2") (pintype "passive"))
      (node (ref "C3") (pin "2") (pinfunction "2_2") (pintype "passive"))
      (node (ref "C4") (pin "2") (pinfunction "2_2") (pintype "passive"))
      (node (ref "C5") (pin "2") (pinfunction "2_2") (pintype "passive"))
      (node (ref "C6") (pin "2") (pinfunction "2_2") (pintype "passive"))
      (node (ref "C81") (pin "2") (pinfunction "2_2") (pintype "passive"))
      (node (ref "C85") (pin "2") (pinfunction "2_2") (pintype "passive"))
      (node (ref "LED0") (pin "2") (pinfunction "2_2") (pintype "passive"))
      (node (ref "LED1") (pin "2") (pinfunction "2_2") (pintype "passive"))
      (node (ref "R102") (pin "2") (pinfunction "2_2") (pintype "passive"))
      (node (ref "R105") (pin "2") (pinfunction "2_2") (pintype "passive"))
      (node (ref "R42") (pin "1") (pinfunction "1_1") (pintype "passive"))
      (node (ref "U1") (pin "1") (pinfunction "VBAT_1") (pintype "power_in"))
      (node (ref "U1") (pin "13") (pinfunction "VDDA_13") (pintype "power_in"))
      (node (ref "U1") (pin "19") (pinfunction "VDD_4_19") (pintype "power_in"))
      (node (ref "U1") (pin "32") (pinfunction "VDD_1_32") (pintype "power_in"))
      (node (ref "U1") (pin "48") (pinfunction "VDD_2_48") (pintype "power_in"))
      (node (ref "U1") (pin "64") (pinfunction "VDD_3_64") (pintype "power_in"))
      (node (ref "U10") (pin "10") (pinfunction "VIO_10") (pintype "passive"))
      (node (ref "U11") (pin "10") (pinfunction "VIO_10") (pintype "passive"))
      (node (ref "U14") (pin "10") (pinfunction "GAIN_10") (pintype "passive"))
      (node (ref "U14") (pin "11") (pinfunction "Vlogic_11") (pintype "passive"))
      (node (ref "U44") (pin "8") (pinfunction "VCC_8") (pintype "passive"))
      (node (ref "U45") (pin "8") (pinfunction "VCC_8") (pintype "passive"))
      (node (ref "U8") (pin "5") (pinfunction "VOUT_5") (pintype "passive"))
    )
    (net (code "85") (name "D5V0") (class "Default")
      (node (ref "C57") (pin "2") (pinfunction "2_2") (pintype "passive"))
      (node (ref "C58") (pin "2") (pinfunction "2_2") (pintype "passive"))
      (node (ref "C59") (pin "1") (pinfunction "1_1") (pintype "passive"))
      (node (ref "LCD") (pin "7") (pinfunction "7_7") (pintype "passive"))
      (node (ref "LCD") (pin "8") (pinfunction "8_8") (pintype "passive"))
      (node (ref "U8") (pin "1") (pinfunction "VIN_1") (pintype "passive"))
      (node (ref "U8") (pin "3") (pinfunction "EN_3") (pintype "passive"))
    )
    (net (code "86") (name "DGND") (class "Default")
      (node (ref "C1") (pin "1") (pinfunction "1_1") (pintype "passive"))
      (node (ref "C108") (pin "1") (pinfunction "1_1") (pintype "passive"))
      (node (ref "C2") (pin "1") (pinfunction "1_1") (pintype "passive"))
      (node (ref "C22") (pin "1") (pinfunction "1_1") (pintype "passive"))
      (node (ref "C23") (pin "1") (pinfunction "1_1") (pintype "passive"))
      (node (ref "C29") (pin "1") (pinfunction "1_1") (pintype "passive"))
      (node (ref "C3") (pin "1") (pinfunction "1_1") (pintype "passive"))
      (node (ref "C4") (pin "1") (pinfunction "1_1") (pintype "passive"))
      (node (ref "C5") (pin "1") (pinfunction "1_1") (pintype "passive"))
      (node (ref "C57") (pin "1") (pinfunction "1_1") (pintype "passive"))
      (node (ref "C58") (pin "1") (pinfunction "1_1") (pintype "passive"))
      (node (ref "C59") (pin "2") (pinfunction "2_2") (pintype "passive"))
      (node (ref "C6") (pin "1") (pinfunction "1_1") (pintype "passive"))
      (node (ref "C81") (pin "1") (pinfunction "1_1") (pintype "passive"))
      (node (ref "C85") (pin "1") (pinfunction "1_1") (pintype "passive"))
      (node (ref "DL") (pin "5") (pinfunction "VSS_5") (pintype "passive"))
      (node (ref "L1") (pin "2") (pinfunction "2_2") (pintype "passive"))
      (node (ref "L3") (pin "2") (pinfunction "2_2") (pintype "passive"))
      (node (ref "LCD") (pin "1") (pinfunction "1_1") (pintype "passive"))
      (node (ref "LCD") (pin "2") (pinfunction "2_2") (pintype "passive"))
      (node (ref "R101") (pin "2") (pinfunction "2_2") (pintype "passive"))
      (node (ref "R104") (pin "2") (pinfunction "2_2") (pintype "passive"))
      (node (ref "R2") (pin "2") (pinfunction "2_2") (pintype "passive"))
      (node (ref "R66") (pin "1") (pinfunction "1_1") (pintype "passive"))
      (node (ref "RS485_2") (pin "3") (pinfunction "3_3") (pintype "passive"))
      (node (ref "U1") (pin "12") (pinfunction "VSSA_12") (pintype "power_in"))
      (node (ref "U1") (pin "18") (pinfunction "VSS_4_18") (pintype "power_in"))
      (node (ref "U1") (pin "31") (pinfunction "VSS_1_31") (pintype "power_in"))
      (node (ref "U1") (pin "47") (pinfunction "VSS_2_47") (pintype "power_in"))
      (node (ref "U1") (pin "63") (pinfunction "VSS_3_63") (pintype "power_in"))
      (node (ref "U44") (pin "5") (pinfunction "GND_5") (pintype "passive"))
      (node (ref "U45") (pin "5") (pinfunction "GND_5") (pintype "passive"))
      (node (ref "U8") (pin "2") (pinfunction "GND_2") (pintype "passive"))
      (node (ref "USB") (pin "4") (pinfunction "GND_4") (pintype "passive"))
      (node (ref "X1") (pin "2") (pinfunction "GND_2") (pintype "passive"))
    )
    (net (code "87") (name "GUARD") (class "Default")
      (node (ref "FORCE_H") (pin "2") (pinfunction "Y_2") (pintype "passive"))
      (node (ref "GUARD") (pin "1") (pinfunction "X_1") (pintype "passive"))
      (node (ref "R28") (pin "2") (pinfunction "2_2") (pintype "passive"))
      (node (ref "SENSE_H") (pin "2") (pinfunction "Y_2") (pintype "passive"))
    )
    (net (code "88") (name "Net-(C21-Pad1)") (class "Default")
      (node (ref "C21") (pin "1") (pinfunction "1_1") (pintype "passive"))
      (node (ref "R16") (pin "2") (pinfunction "2_2") (pintype "passive"))
    )
    (net (code "89") (name "Net-(C70-Pad2)") (class "Default")
      (node (ref "C70") (pin "2") (pinfunction "2_2") (pintype "passive"))
      (node (ref "K1") (pin "4") (pinfunction "4_4") (pintype "passive"))
      (node (ref "R31") (pin "2") (pinfunction "2_2") (pintype "passive"))
    )
    (net (code "90") (name "Net-(C71-Pad2)") (class "Default")
      (node (ref "C71") (pin "2") (pinfunction "2_2") (pintype "passive"))
      (node (ref "K2") (pin "4") (pinfunction "4_4") (pintype "passive"))
      (node (ref "R32") (pin "2") (pinfunction "2_2") (pintype "passive"))
    )
    (net (code "91") (name "Net-(C72-Pad2)") (class "Default")
      (node (ref "C72") (pin "2") (pinfunction "2_2") (pintype "passive"))
      (node (ref "K3") (pin "4") (pinfunction "4_4") (pintype "passive"))
      (node (ref "R33") (pin "2") (pinfunction "2_2") (pintype "passive"))
    )
    (net (code "92") (name "Net-(C73-Pad2)") (class "Default")
      (node (ref "C73") (pin "2") (pinfunction "2_2") (pintype "passive"))
      (node (ref "K4") (pin "4") (pinfunction "4_4") (pintype "passive"))
      (node (ref "R34") (pin "2") (pinfunction "2_2") (pintype "passive"))
    )
    (net (code "93") (name "Net-(C74-Pad2)") (class "Default")
      (node (ref "C74") (pin "2") (pinfunction "2_2") (pintype "passive"))
      (node (ref "K5") (pin "4") (pinfunction "4_4") (pintype "passive"))
      (node (ref "R35") (pin "2") (pinfunction "2_2") (pintype "passive"))
    )
    (net (code "94") (name "Net-(C75-Pad2)") (class "Default")
      (node (ref "C75") (pin "2") (pinfunction "2_2") (pintype "passive"))
      (node (ref "K6") (pin "4") (pinfunction "4_4") (pintype "passive"))
      (node (ref "R36") (pin "2") (pinfunction "2_2") (pintype "passive"))
    )
    (net (code "95") (name "Net-(C76-Pad2)") (class "Default")
      (node (ref "C76") (pin "2") (pinfunction "2_2") (pintype "passive"))
      (node (ref "K7") (pin "4") (pinfunction "4_4") (pintype "passive"))
      (node (ref "R37") (pin "2") (pinfunction "2_2") (pintype "passive"))
    )
    (net (code "96") (name "Net-(C77-Pad2)") (class "Default")
      (node (ref "C77") (pin "2") (pinfunction "2_2") (pintype "passive"))
      (node (ref "K8") (pin "4") (pinfunction "4_4") (pintype "passive"))
      (node (ref "R38") (pin "2") (pinfunction "2_2") (pintype "passive"))
    )
    (net (code "97") (name "Net-(C78-Pad2)") (class "Default")
      (node (ref "C78") (pin "2") (pinfunction "2_2") (pintype "passive"))
      (node (ref "K9") (pin "4") (pinfunction "4_4") (pintype "passive"))
      (node (ref "R39") (pin "2") (pinfunction "2_2") (pintype "passive"))
    )
    (net (code "98") (name "Net-(C79-Pad2)") (class "Default")
      (node (ref "C79") (pin "2") (pinfunction "2_2") (pintype "passive"))
      (node (ref "K10") (pin "4") (pinfunction "4_4") (pintype "passive"))
      (node (ref "R40") (pin "2") (pinfunction "2_2") (pintype "passive"))
    )
    (net (code "99") (name "Net-(J1-Pad5)") (class "Default")
      (node (ref "J1") (pin "5") (pinfunction "5_5") (pintype "passive"))
      (node (ref "R66") (pin "2") (pinfunction "2_2") (pintype "passive"))
    )
    (net (code "100") (name "Net-(K1-Pad3)") (class "Default")
      (node (ref "K1") (pin "3") (pinfunction "3_3") (pintype "passive"))
      (node (ref "K1") (pin "6") (pinfunction "6_6") (pintype "passive"))
    )
    (net (code "101") (name "Net-(K2-Pad3)") (class "Default")
      (node (ref "K2") (pin "3") (pinfunction "3_3") (pintype "passive"))
      (node (ref "K2") (pin "6") (pinfunction "6_6") (pintype "passive"))
    )
    (net (code "102") (name "Net-(K3-Pad3)") (class "Default")
      (node (ref "K3") (pin "3") (pinfunction "3_3") (pintype "passive"))
      (node (ref "K3") (pin "6") (pinfunction "6_6") (pintype "passive"))
    )
    (net (code "103") (name "Net-(K4-Pad3)") (class "Default")
      (node (ref "K4") (pin "3") (pinfunction "3_3") (pintype "passive"))
      (node (ref "K4") (pin "6") (pinfunction "6_6") (pintype "passive"))
    )
    (net (code "104") (name "Net-(K5-Pad3)") (class "Default")
      (node (ref "K5") (pin "3") (pinfunction "3_3") (pintype "passive"))
      (node (ref "K5") (pin "6") (pinfunction "6_6") (pintype "passive"))
    )
    (net (code "105") (name "Net-(K6-Pad3)") (class "Default")
      (node (ref "K6") (pin "3") (pinfunction "3_3") (pintype "passive"))
      (node (ref "K6") (pin "6") (pinfunction "6_6") (pintype "passive"))
    )
    (net (code "106") (name "Net-(K7-Pad3)") (class "Default")
      (node (ref "K7") (pin "3") (pinfunction "3_3") (pintype "passive"))
      (node (ref "K7") (pin "6") (pinfunction "6_6") (pintype "passive"))
    )
    (net (code "107") (name "Net-(K8-Pad3)") (class "Default")
      (node (ref "K8") (pin "3") (pinfunction "3_3") (pintype "passive"))
      (node (ref "K8") (pin "6") (pinfunction "6_6") (pintype "passive"))
    )
    (net (code "108") (name "Net-(K9-Pad3)") (class "Default")
      (node (ref "K9") (pin "3") (pinfunction "3_3") (pintype "passive"))
      (node (ref "K9") (pin "6") (pinfunction "6_6") (pintype "passive"))
    )
    (net (code "109") (name "Net-(K10-Pad3)") (class "Default")
      (node (ref "K10") (pin "3") (pinfunction "3_3") (pintype "passive"))
      (node (ref "K10") (pin "6") (pinfunction "6_6") (pintype "passive"))
    )
    (net (code "110") (name "Net-(K13-Pad3)") (class "Default")
      (node (ref "K13") (pin "3") (pintype "passive"))
      (node (ref "R44") (pin "1") (pinfunction "1_1") (pintype "passive"))
    )
    (net (code "111") (name "Net-(K14-Pad3)") (class "Default")
      (node (ref "K14") (pin "3") (pintype "passive"))
      (node (ref "R45") (pin "1") (pinfunction "1_1") (pintype "passive"))
    )
    (net (code "112") (name "Net-(L1-Pad1)") (class "Default")
      (node (ref "L1") (pin "1") (pinfunction "1_1") (pintype "passive"))
      (node (ref "USB") (pin "5") (pinfunction "VSS_5") (pintype "passive"))
      (node (ref "USB") (pin "6") (pinfunction "VSS_6") (pintype "passive"))
    )
    (net (code "113") (name "Net-(LED0-Pad1)") (class "Default")
      (node (ref "LED0") (pin "1") (pinfunction "1_1") (pintype "passive"))
      (node (ref "R68") (pin "1") (pinfunction "1_1") (pintype "passive"))
    )
    (net (code "114") (name "Net-(LED1-Pad1)") (class "Default")
      (node (ref "LED1") (pin "1") (pinfunction "1_1") (pintype "passive"))
      (node (ref "R69") (pin "1") (pinfunction "1_1") (pintype "passive"))
    )
    (net (code "115") (name "Net-(U1-BOOT0)") (class "Default")
      (node (ref "R2") (pin "1") (pinfunction "1_1") (pintype "passive"))
      (node (ref "U1") (pin "60") (pinfunction "BOOT0_60") (pintype "input"))
    )
    (net (code "116") (name "Net-(U1-OSC_IN{slash}PD0)") (class "Default")
      (node (ref "U1") (pin "5") (pinfunction "OSC_IN/PD0_5") (pintype "input"))
      (node (ref "X1") (pin "1") (pinfunction "OSC1_1") (pintype "passive"))
    )
    (net (code "117") (name "Net-(U1-OSC_OUT{slash}PD1)") (class "Default")
      (node (ref "R1") (pin "2") (pinfunction "2_2") (pintype "passive"))
      (node (ref "U1") (pin "6") (pinfunction "OSC_OUT/PD1_6") (pintype "output"))
    )
    (net (code "118") (name "Net-(U2-BW)") (class "Default")
      (node (ref "R27") (pin "2") (pinfunction "2_2") (pintype "passive"))
      (node (ref "U2") (pin "1") (pinfunction "BW_1") (pintype "passive"))
    )
    (net (code "119") (name "Net-(U2-Vin)") (class "Default")
      (node (ref "C20") (pin "2") (pinfunction "2_2") (pintype "passive"))
      (node (ref "R10") (pin "2") (pinfunction "2_2") (pintype "passive"))
      (node (ref "U2") (pin "2") (pinfunction "Vin_2") (pintype "passive"))
    )
    (net (code "120") (name "Net-(U3-+IN_B)") (class "Default")
      (node (ref "R16") (pin "1") (pinfunction "1_1") (pintype "passive"))
      (node (ref "U3") (pin "5") (pinfunction "+IN_B_5") (pintype "passive"))
      (node (ref "U4") (pin "1") (pinfunction "Out_A_1") (pintype "passive"))
    )
    (net (code "121") (name "Net-(U3--IN_A)") (class "Default")
      (node (ref "K11") (pin "4") (pintype "passive"))
      (node (ref "R17") (pin "1") (pinfunction "1_1") (pintype "passive"))
      (node (ref "R18") (pin "2") (pinfunction "2_2") (pintype "passive"))
      (node (ref "U3") (pin "2") (pinfunction "-IN_A_2") (pintype "input"))
    )
    (net (code "122") (name "Net-(U3--IN_B)") (class "Default")
      (node (ref "R10") (pin "1") (pinfunction "1_1") (pintype "passive"))
      (node (ref "U3") (pin "6") (pinfunction "-IN_B_6") (pintype "passive"))
      (node (ref "U3") (pin "7") (pinfunction "Out_B_7") (pintype "passive"))
    )
    (net (code "123") (name "Net-(U3-Out_A)") (class "Default")
      (node (ref "K11") (pin "1") (pintype "passive"))
      (node (ref "R18") (pin "1") (pinfunction "1_1") (pintype "passive"))
      (node (ref "U3") (pin "1") (pinfunction "Out_A_1") (pintype "passive"))
      (node (ref "U4") (pin "3") (pinfunction "+IN_A_3") (pintype "input"))
    )
    (net (code "124") (name "Net-(U4--IN_A)") (class "Default")
      (node (ref "K12") (pin "3") (pintype "passive"))
      (node (ref "U4") (pin "2") (pinfunction "-IN_A_2") (pintype "input"))
    )
    (net (code "125") (name "Net-(U4--IN_B)") (class "Default")
      (node (ref "R28") (pin "1") (pinfunction "1_1") (pintype "passive"))
      (node (ref "U4") (pin "6") (pinfunction "-IN_B_6") (pintype "passive"))
      (node (ref "U4") (pin "7") (pinfunction "Out_B_7") (pintype "passive"))
    )
    (net (code "126") (name "Net-(U6-IN+)") (class "Default")
      (node (ref "C30") (pin "2") (pinfunction "2_2") (pintype "passive"))
      (node (ref "C32") (pin "1") (pinfunction "1_1") (pintype "passive"))
      (node (ref "R21") (pin "1") (pinfunction "1_1") (pintype "passive"))
      (node (ref "U6") (pin "4") (pinfunction "IN+_4") (pintype "passive"))
    )
    (net (code "127") (name "Net-(U6-IN-)") (class "Default")
      (node (ref "C30") (pin "1") (pinfunction "1_1") (pintype "passive"))
      (node (ref "C31") (pin "2") (pinfunction "2_2") (pintype "passive"))
      (node (ref "R19") (pin "1") (pinfunction "1_1") (pintype "passive"))
      (node (ref "U6") (pin "1") (pinfunction "IN-_1") (pintype "passive"))
    )
    (net (code "128") (name "Net-(U7-IN+)") (class "Default")
      (node (ref "C34") (pin "2") (pinfunction "2_2") (pintype "passive"))
      (node (ref "C35") (pin "1") (pinfunction "1_1") (pintype "passive"))
      (node (ref "R14") (pin "2") (pinfunction "2_2") (pintype "passive"))
      (node (ref "U7") (pin "4") (pinfunction "IN+_4") (pintype "passive"))
    )
    (net (code "129") (name "Net-(U7-IN-)") (class "Default")
      (node (ref "C33") (pin "2") (pinfunction "2_2") (pintype "passive"))
      (node (ref "C34") (pin "1") (pinfunction "1_1") (pintype "passive"))
      (node (ref "R12") (pin "2") (pinfunction "2_2") (pintype "passive"))
      (node (ref "U7") (pin "1") (pinfunction "IN-_1") (pintype "passive"))
    )
    (net (code "130") (name "Net-(U8-BP)") (class "Default")
      (node (ref "C23") (pin "2") (pinfunction "2_2") (pintype "passive"))
      (node (ref "U8") (pin "4") (pinfunction "BP_4") (pintype "passive"))
    )
    (net (code "131") (name "Net-(U10-IN+)") (class "Default")
      (node (ref "C80") (pin "1") (pinfunction "1_1") (pintype "passive"))
      (node (ref "R30") (pin "2") (pinfunction "2_2") (pintype "passive"))
      (node (ref "U10") (pin "3") (pinfunction "IN+_3") (pintype "passive"))
    )
    (net (code "132") (name "Net-(U11-IN+)") (class "Default")
      (node (ref "C84") (pin "2") (pinfunction "2_2") (pintype "passive"))
      (node (ref "R29") (pin "2") (pinfunction "2_2") (pintype "passive"))
      (node (ref "U11") (pin "3") (pinfunction "IN+_3") (pintype "passive"))
    )
    (net (code "133") (name "Net-(U12-Vout)") (class "Default")
      (node (ref "C90") (pin "2") (pinfunction "2_2") (pintype "passive"))
      (node (ref "U12") (pin "6") (pinfunction "Vout_6") (pintype "passive"))
      (node (ref "U13") (pin "3") (pinfunction "+IN_A_3") (pintype "input"))
    )
    (net (code "134") (name "Net-(U13-+IN_B)") (class "Default")
      (node (ref "R61") (pin "2") (pinfunction "2_2") (pintype "passive"))
      (node (ref "R62") (pin "1") (pinfunction "1_1") (pintype "passive"))
      (node (ref "U13") (pin "5") (pinfunction "+IN_B_5") (pintype "passive"))
    )
    (net (code "135") (name "Net-(U14-Vref)") (class "Default")
      (node (ref "C49") (pin "1") (pinfunction "1_1") (pintype "passive"))
      (node (ref "U14") (pin "1") (pinfunction "Vref_1") (pintype "passive"))
    )
    (net (code "136") (name "Net-(U17-+IN)") (class "Default")
      (node (ref "R49") (pin "1") (pinfunction "1_1") (pintype "passive"))
      (node (ref "R50") (pin "2") (pinfunction "2_2") (pintype "passive"))
      (node (ref "U17") (pin "10") (pinfunction "+IN_10") (pintype "passive"))
    )
    (net (code "137") (name "Net-(U17-OUT)") (class "Default")
      (node (ref "R30") (pin "1") (pinfunction "1_1") (pintype "passive"))
      (node (ref "U17") (pin "7") (pinfunction "OUT_7") (pintype "passive"))
    )
    (net (code "138") (name "Net-(U18-+IN)") (class "Default")
      (node (ref "R51") (pin "1") (pinfunction "1_1") (pintype "passive"))
      (node (ref "R52") (pin "2") (pinfunction "2_2") (pintype "passive"))
      (node (ref "U18") (pin "10") (pinfunction "+IN_10") (pintype "passive"))
    )
    (net (code "139") (name "Net-(U18-OUT)") (class "Default")
      (node (ref "R29") (pin "1") (pinfunction "1_1") (pintype "passive"))
      (node (ref "U18") (pin "7") (pinfunction "OUT_7") (pintype "passive"))
    )
    (net (code "140") (name "Net-(U23-+IN_A)") (class "Default")
      (node (ref "R22") (pin "2") (pinfunction "2_2") (pintype "passive"))
      (node (ref "R23") (pin "2") (pinfunction "2_2") (pintype "passive"))
      (node (ref "U23") (pin "3") (pinfunction "+IN_A_3") (pintype "input"))
    )
    (net (code "141") (name "Net-(U23--IN_A)") (class "Default")
      (node (ref "C154") (pin "1") (pinfunction "1_1") (pintype "passive"))
      (node (ref "R24") (pin "2") (pinfunction "2_2") (pintype "passive"))
      (node (ref "R25") (pin "1") (pinfunction "1_1") (pintype "passive"))
      (node (ref "U23") (pin "2") (pinfunction "-IN_A_2") (pintype "input"))
    )
    (net (code "142") (name "Net-(U23--IN_B)") (class "Default")
      (node (ref "U23") (pin "6") (pinfunction "-IN_B_6") (pintype "passive"))
      (node (ref "U23") (pin "7") (pinfunction "Out_B_7") (pintype "passive"))
    )
    (net (code "143") (name "Net-(U44-A)") (class "Default")
      (node (ref "J1") (pin "3") (pinfunction "3_3") (pintype "passive"))
      (node (ref "R100") (pin "2") (pinfunction "2_2") (pintype "passive"))
      (node (ref "R102") (pin "1") (pinfunction "1_1") (pintype "passive"))
      (node (ref "U44") (pin "6") (pinfunction "A_6") (pintype "passive"))
    )
    (net (code "144") (name "Net-(U44-B)") (class "Default")
      (node (ref "J1") (pin "2") (pinfunction "2_2") (pintype "passive"))
      (node (ref "R100") (pin "1") (pinfunction "1_1") (pintype "passive"))
      (node (ref "R101") (pin "1") (pinfunction "1_1") (pintype "passive"))
      (node (ref "U44") (pin "7") (pinfunction "B_7") (pintype "passive"))
    )
    (net (code "145") (name "Net-(U45-A)") (class "Default")
      (node (ref "R103") (pin "2") (pinfunction "2_2") (pintype "passive"))
      (node (ref "R105") (pin "1") (pinfunction "1_1") (pintype "passive"))
      (node (ref "RS485_2") (pin "2") (pinfunction "2_2") (pintype "passive"))
      (node (ref "U45") (pin "6") (pinfunction "A_6") (pintype "passive"))
    )
    (net (code "146") (name "Net-(U45-B)") (class "Default")
      (node (ref "R103") (pin "1") (pinfunction "1_1") (pintype "passive"))
      (node (ref "R104") (pin "1") (pinfunction "1_1") (pintype "passive"))
      (node (ref "RS485_2") (pin "1") (pinfunction "1_1") (pintype "passive"))
      (node (ref "U45") (pin "7") (pinfunction "B_7") (pintype "passive"))
    )
    (net (code "147") (name "Net-(USB-D+)") (class "Default")
      (node (ref "R41") (pin "1") (pinfunction "1_1") (pintype "passive"))
      (node (ref "USB") (pin "3") (pinfunction "D+_3") (pintype "passive"))
    )
    (net (code "148") (name "Net-(USB-D-)") (class "Default")
      (node (ref "R43") (pin "1") (pinfunction "1_1") (pintype "passive"))
      (node (ref "USB") (pin "2") (pinfunction "D-_2") (pintype "passive"))
    )
    (net (code "149") (name "Net-(X1-OSC2)") (class "Default")
      (node (ref "R1") (pin "1") (pinfunction "1_1") (pintype "passive"))
      (node (ref "X1") (pin "3") (pinfunction "OSC2_3") (pintype "passive"))
    )
    (net (code "150") (name "unconnected-(DL-Vcc-Pad1)") (class "Default")
      (node (ref "DL") (pin "1") (pinfunction "Vcc_1") (pintype "passive"))
    )
    (net (code "151") (name "unconnected-(J1-MH1-Pad10)") (class "Default")
      (node (ref "J1") (pin "10") (pinfunction "MH1_10") (pintype "passive"))
    )
    (net (code "152") (name "unconnected-(J1-MH2-Pad11)") (class "Default")
      (node (ref "J1") (pin "11") (pinfunction "MH2_11") (pintype "passive"))
    )
    (net (code "153") (name "unconnected-(J1-Pad1)") (class "Default")
      (node (ref "J1") (pin "1") (pinfunction "1_1") (pintype "passive"))
    )
    (net (code "154") (name "unconnected-(J1-Pad4)") (class "Default")
      (node (ref "J1") (pin "4") (pinfunction "4_4") (pintype "passive"))
    )
    (net (code "155") (name "unconnected-(J1-Pad6)") (class "Default")
      (node (ref "J1") (pin "6") (pinfunction "6_6") (pintype "passive"))
    )
    (net (code "156") (name "unconnected-(J1-Pad7)") (class "Default")
      (node (ref "J1") (pin "7") (pinfunction "7_7") (pintype "passive"))
    )
    (net (code "157") (name "unconnected-(J1-Pad8)") (class "Default")
      (node (ref "J1") (pin "8") (pinfunction "8_8") (pintype "passive"))
    )
    (net (code "158") (name "unconnected-(J1-Pad9)") (class "Default")
      (node (ref "J1") (pin "9") (pinfunction "9_9") (pintype "passive"))
    )
    (net (code "159") (name "unconnected-(K1-Pad2)") (class "Default")
      (node (ref "K1") (pin "2") (pinfunction "2_2") (pintype "passive"))
    )
    (net (code "160") (name "unconnected-(K1-Pad7)") (class "Default")
      (node (ref "K1") (pin "7") (pinfunction "7_7") (pintype "passive"))
    )
    (net (code "161") (name "unconnected-(K2-Pad2)") (class "Default")
      (node (ref "K2") (pin "2") (pinfunction "2_2") (pintype "passive"))
    )
    (net (code "162") (name "unconnected-(K2-Pad7)") (class "Default")
      (node (ref "K2") (pin "7") (pinfunction "7_7") (pintype "passive"))
    )
    (net (code "163") (name "unconnected-(K3-Pad2)") (class "Default")
      (node (ref "K3") (pin "2") (pinfunction "2_2") (pintype "passive"))
    )
    (net (code "164") (name "unconnected-(K3-Pad7)") (class "Default")
      (node (ref "K3") (pin "7") (pinfunction "7_7") (pintype "passive"))
    )
    (net (code "165") (name "unconnected-(K4-Pad2)") (class "Default")
      (node (ref "K4") (pin "2") (pinfunction "2_2") (pintype "passive"))
    )
    (net (code "166") (name "unconnected-(K4-Pad7)") (class "Default")
      (node (ref "K4") (pin "7") (pinfunction "7_7") (pintype "passive"))
    )
    (net (code "167") (name "unconnected-(K5-Pad2)") (class "Default")
      (node (ref "K5") (pin "2") (pinfunction "2_2") (pintype "passive"))
    )
    (net (code "168") (name "unconnected-(K5-Pad7)") (class "Default")
      (node (ref "K5") (pin "7") (pinfunction "7_7") (pintype "passive"))
    )
    (net (code "169") (name "unconnected-(K6-Pad2)") (class "Default")
      (node (ref "K6") (pin "2") (pinfunction "2_2") (pintype "passive"))
    )
    (net (code "170") (name "unconnected-(K6-Pad7)") (class "Default")
      (node (ref "K6") (pin "7") (pinfunction "7_7") (pintype "passive"))
    )
    (net (code "171") (name "unconnected-(K7-Pad2)") (class "Default")
      (node (ref "K7") (pin "2") (pinfunction "2_2") (pintype "passive"))
    )
    (net (code "172") (name "unconnected-(K7-Pad7)") (class "Default")
      (node (ref "K7") (pin "7") (pinfunction "7_7") (pintype "passive"))
    )
    (net (code "173") (name "unconnected-(K8-Pad2)") (class "Default")
      (node (ref "K8") (pin "2") (pinfunction "2_2") (pintype "passive"))
    )
    (net (code "174") (name "unconnected-(K8-Pad7)") (class "Default")
      (node (ref "K8") (pin "7") (pinfunction "7_7") (pintype "passive"))
    )
    (net (code "175") (name "unconnected-(K9-Pad2)") (class "Default")
      (node (ref "K9") (pin "2") (pinfunction "2_2") (pintype "passive"))
    )
    (net (code "176") (name "unconnected-(K9-Pad7)") (class "Default")
      (node (ref "K9") (pin "7") (pinfunction "7_7") (pintype "passive"))
    )
    (net (code "177") (name "unconnected-(K10-Pad2)") (class "Default")
      (node (ref "K10") (pin "2") (pinfunction "2_2") (pintype "passive"))
    )
    (net (code "178") (name "unconnected-(K10-Pad7)") (class "Default")
      (node (ref "K10") (pin "7") (pinfunction "7_7") (pintype "passive"))
    )
    (net (code "179") (name "unconnected-(K11-Pad3)") (class "Default")
      (node (ref "K11") (pin "3") (pintype "passive"))
    )
    (net (code "180") (name "unconnected-(K11-Pad6)") (class "Default")
      (node (ref "K11") (pin "6") (pintype "passive"))
    )
    (net (code "181") (name "unconnected-(K12-Pad4)") (class "Default")
      (node (ref "K12") (pin "4") (pintype "passive"))
    )
    (net (code "182") (name "unconnected-(K13-Pad1)") (class "Default")
      (node (ref "K13") (pin "1") (pintype "passive"))
    )
    (net (code "183") (name "unconnected-(K13-Pad4)") (class "Default")
      (node (ref "K13") (pin "4") (pintype "passive"))
    )
    (net (code "184") (name "unconnected-(K14-Pad1)") (class "Default")
      (node (ref "K14") (pin "1") (pintype "passive"))
    )
    (net (code "185") (name "unconnected-(K14-Pad4)") (class "Default")
      (node (ref "K14") (pin "4") (pintype "passive"))
    )
    (net (code "186") (name "unconnected-(K15-Pad3)") (class "Default")
      (node (ref "K15") (pin "3") (pintype "passive"))
    )
    (net (code "187") (name "unconnected-(LCD-Pad6)") (class "Default")
      (node (ref "LCD") (pin "6") (pinfunction "6_6") (pintype "passive+no_connect"))
    )
    (net (code "188") (name "unconnected-(U1-NRST-Pad7)") (class "Default")
      (node (ref "U1") (pin "7") (pinfunction "NRST_7") (pintype "bidirectional"))
    )
    (net (code "189") (name "unconnected-(U1-PC14-OSC32_IN-Pad3)") (class "Default")
      (node (ref "U1") (pin "3") (pinfunction "PC14-OSC32_IN_3") (pintype "bidirectional"))
    )
    (net (code "190") (name "unconnected-(U1-PC15-OSC32_OUT-Pad4)") (class "Default")
      (node (ref "U1") (pin "4") (pinfunction "PC15-OSC32_OUT_4") (pintype "bidirectional"))
    )
    (net (code "191") (name "unconnected-(U12-NC-Pad3)") (class "Default")
      (node (ref "U12") (pin "3") (pinfunction "NC_3") (pintype "passive+no_connect"))
    )
    (net (code "192") (name "unconnected-(U12-NC-Pad7)") (class "Default")
      (node (ref "U12") (pin "7") (pinfunction "NC_7") (pintype "passive+no_connect"))
    )
    (net (code "193") (name "unconnected-(U12-TP-Pad1)") (class "Default")
      (node (ref "U12") (pin "1") (pinfunction "TP_1") (pintype "passive"))
    )
    (net (code "194") (name "unconnected-(U12-TP-Pad8)") (class "Default")
      (node (ref "U12") (pin "8") (pinfunction "TP_8") (pintype "passive"))
    )
    (net (code "195") (name "unconnected-(U12-TRIM-Pad5)") (class "Default")
      (node (ref "U12") (pin "5") (pinfunction "TRIM_5") (pintype "passive+no_connect"))
    )
    (net (code "196") (name "unconnected-(U14-NC-Pad2)") (class "Default")
      (node (ref "U14") (pin "2") (pinfunction "NC_2") (pintype "passive+no_connect"))
    )
    (net (code "197") (name "unconnected-(U14-NC-Pad6)") (class "Default")
      (node (ref "U14") (pin "6") (pinfunction "NC_6") (pintype "passive+no_connect"))
    )
    (net (code "198") (name "unconnected-(U14-SDO-Pad8)") (class "Default")
      (node (ref "U14") (pin "8") (pinfunction "SDO_8") (pintype "passive+no_connect"))
    )
    (net (code "199") (name "unconnected-(USB-Vcc-Pad1)") (class "Default")
      (node (ref "USB") (pin "1") (pinfunction "Vcc_1") (pintype "passive"))
    )
  )
)
